# oresat-backplane-1u.net
KiCad netlist of a schematic drawn in EAGLE
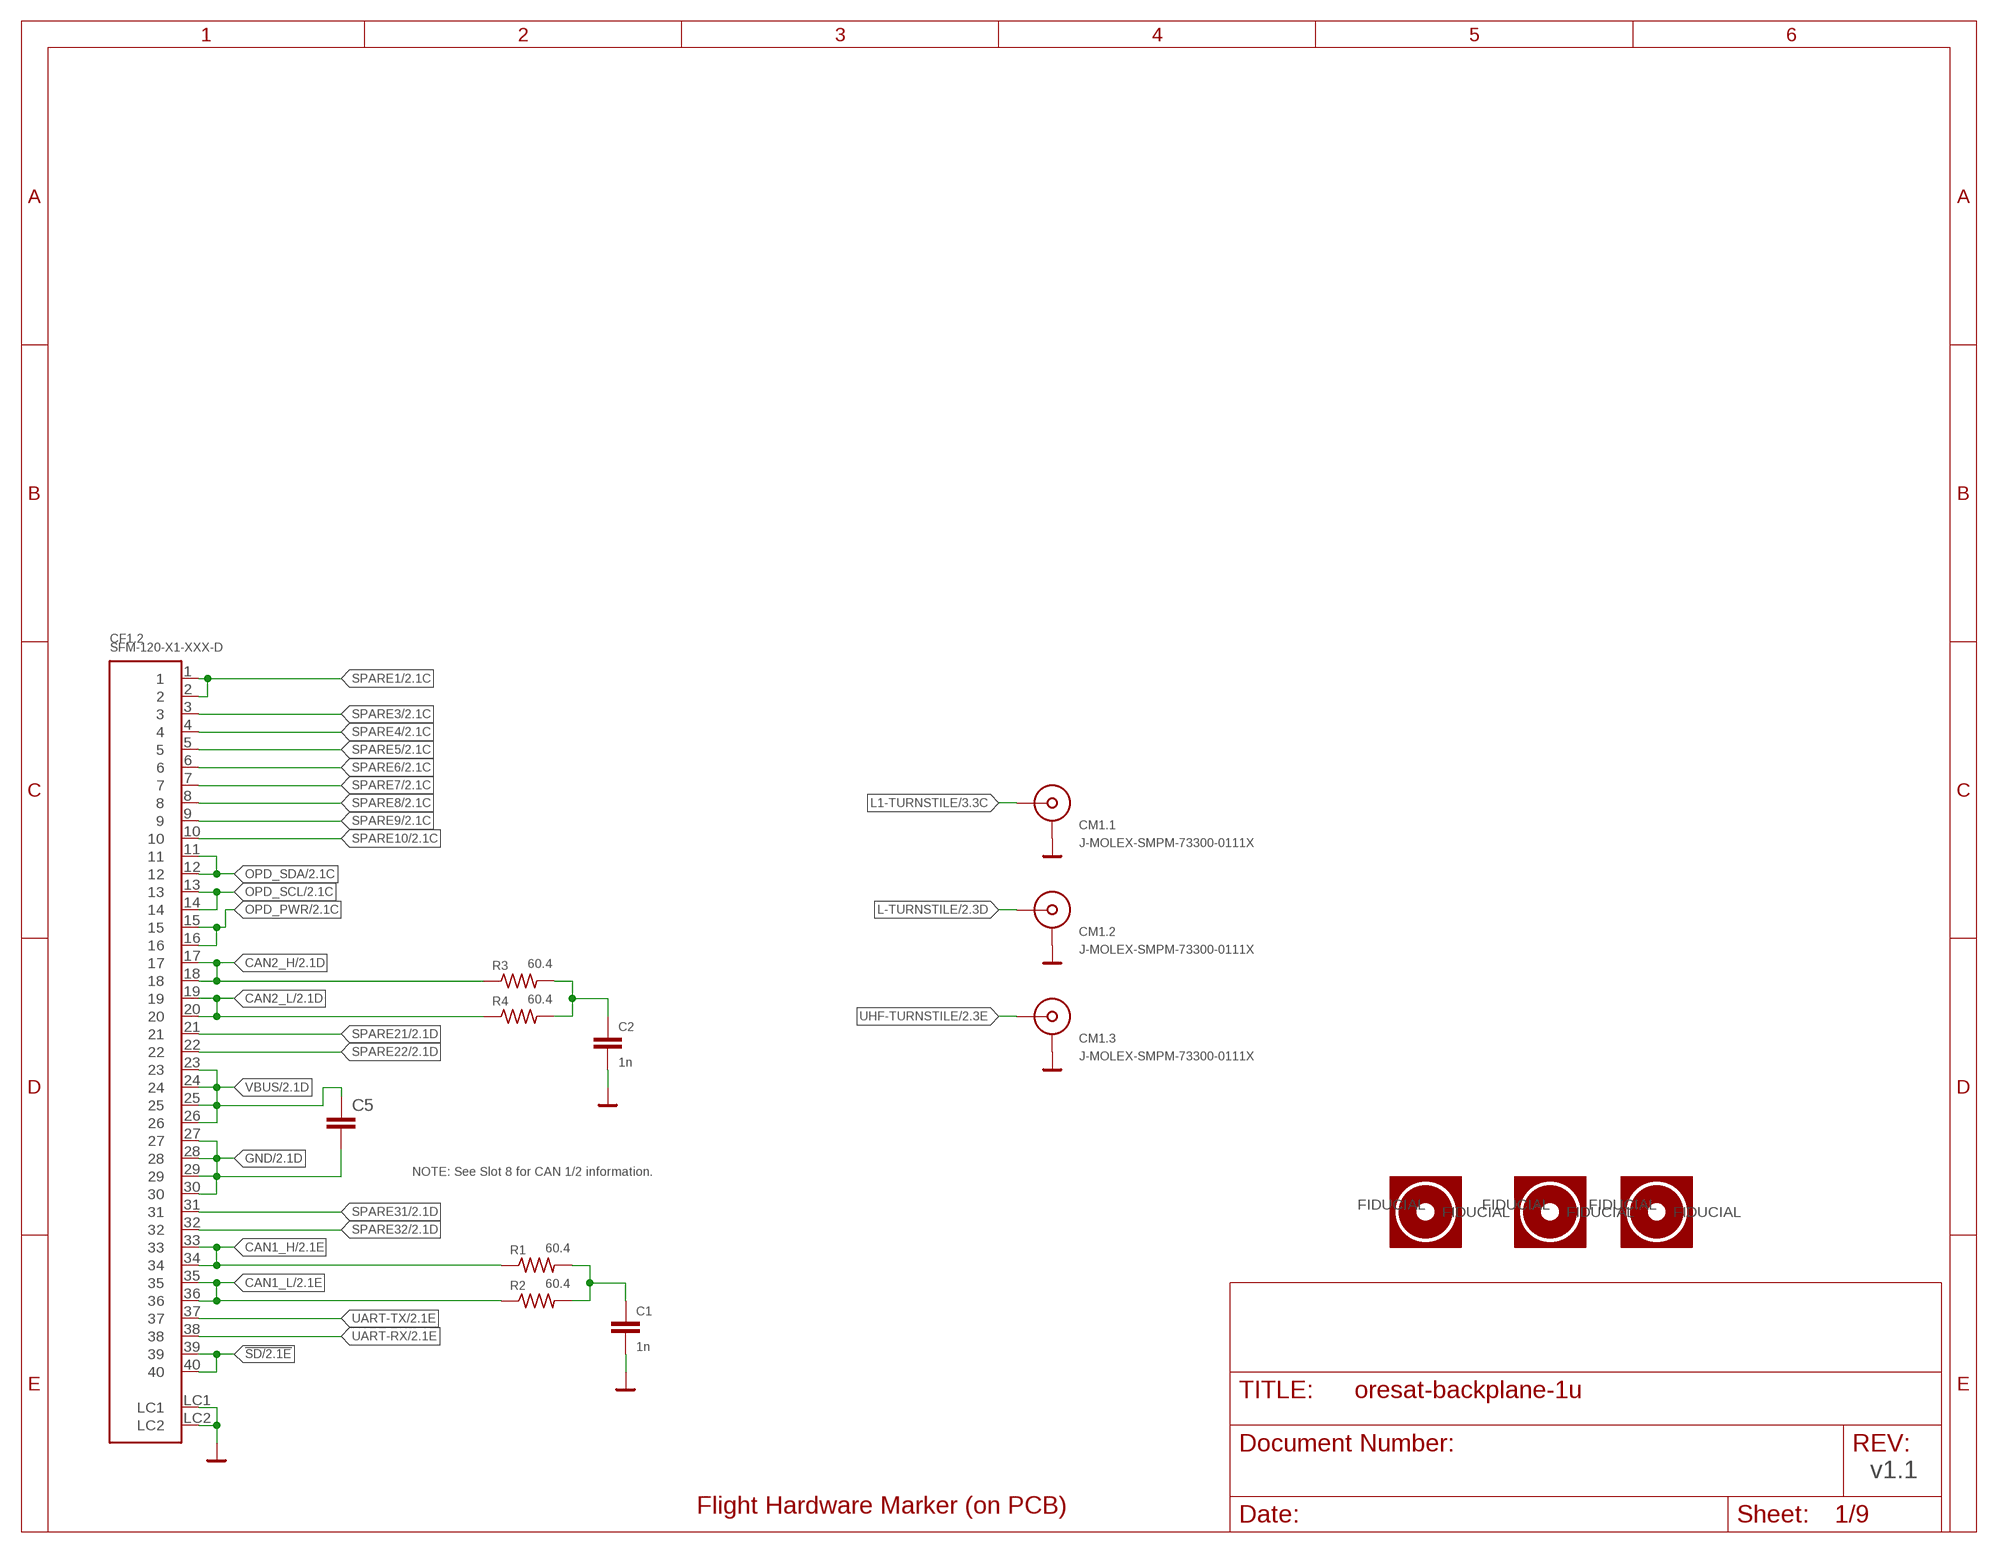
[diagram p0: schematic, sheet 1]
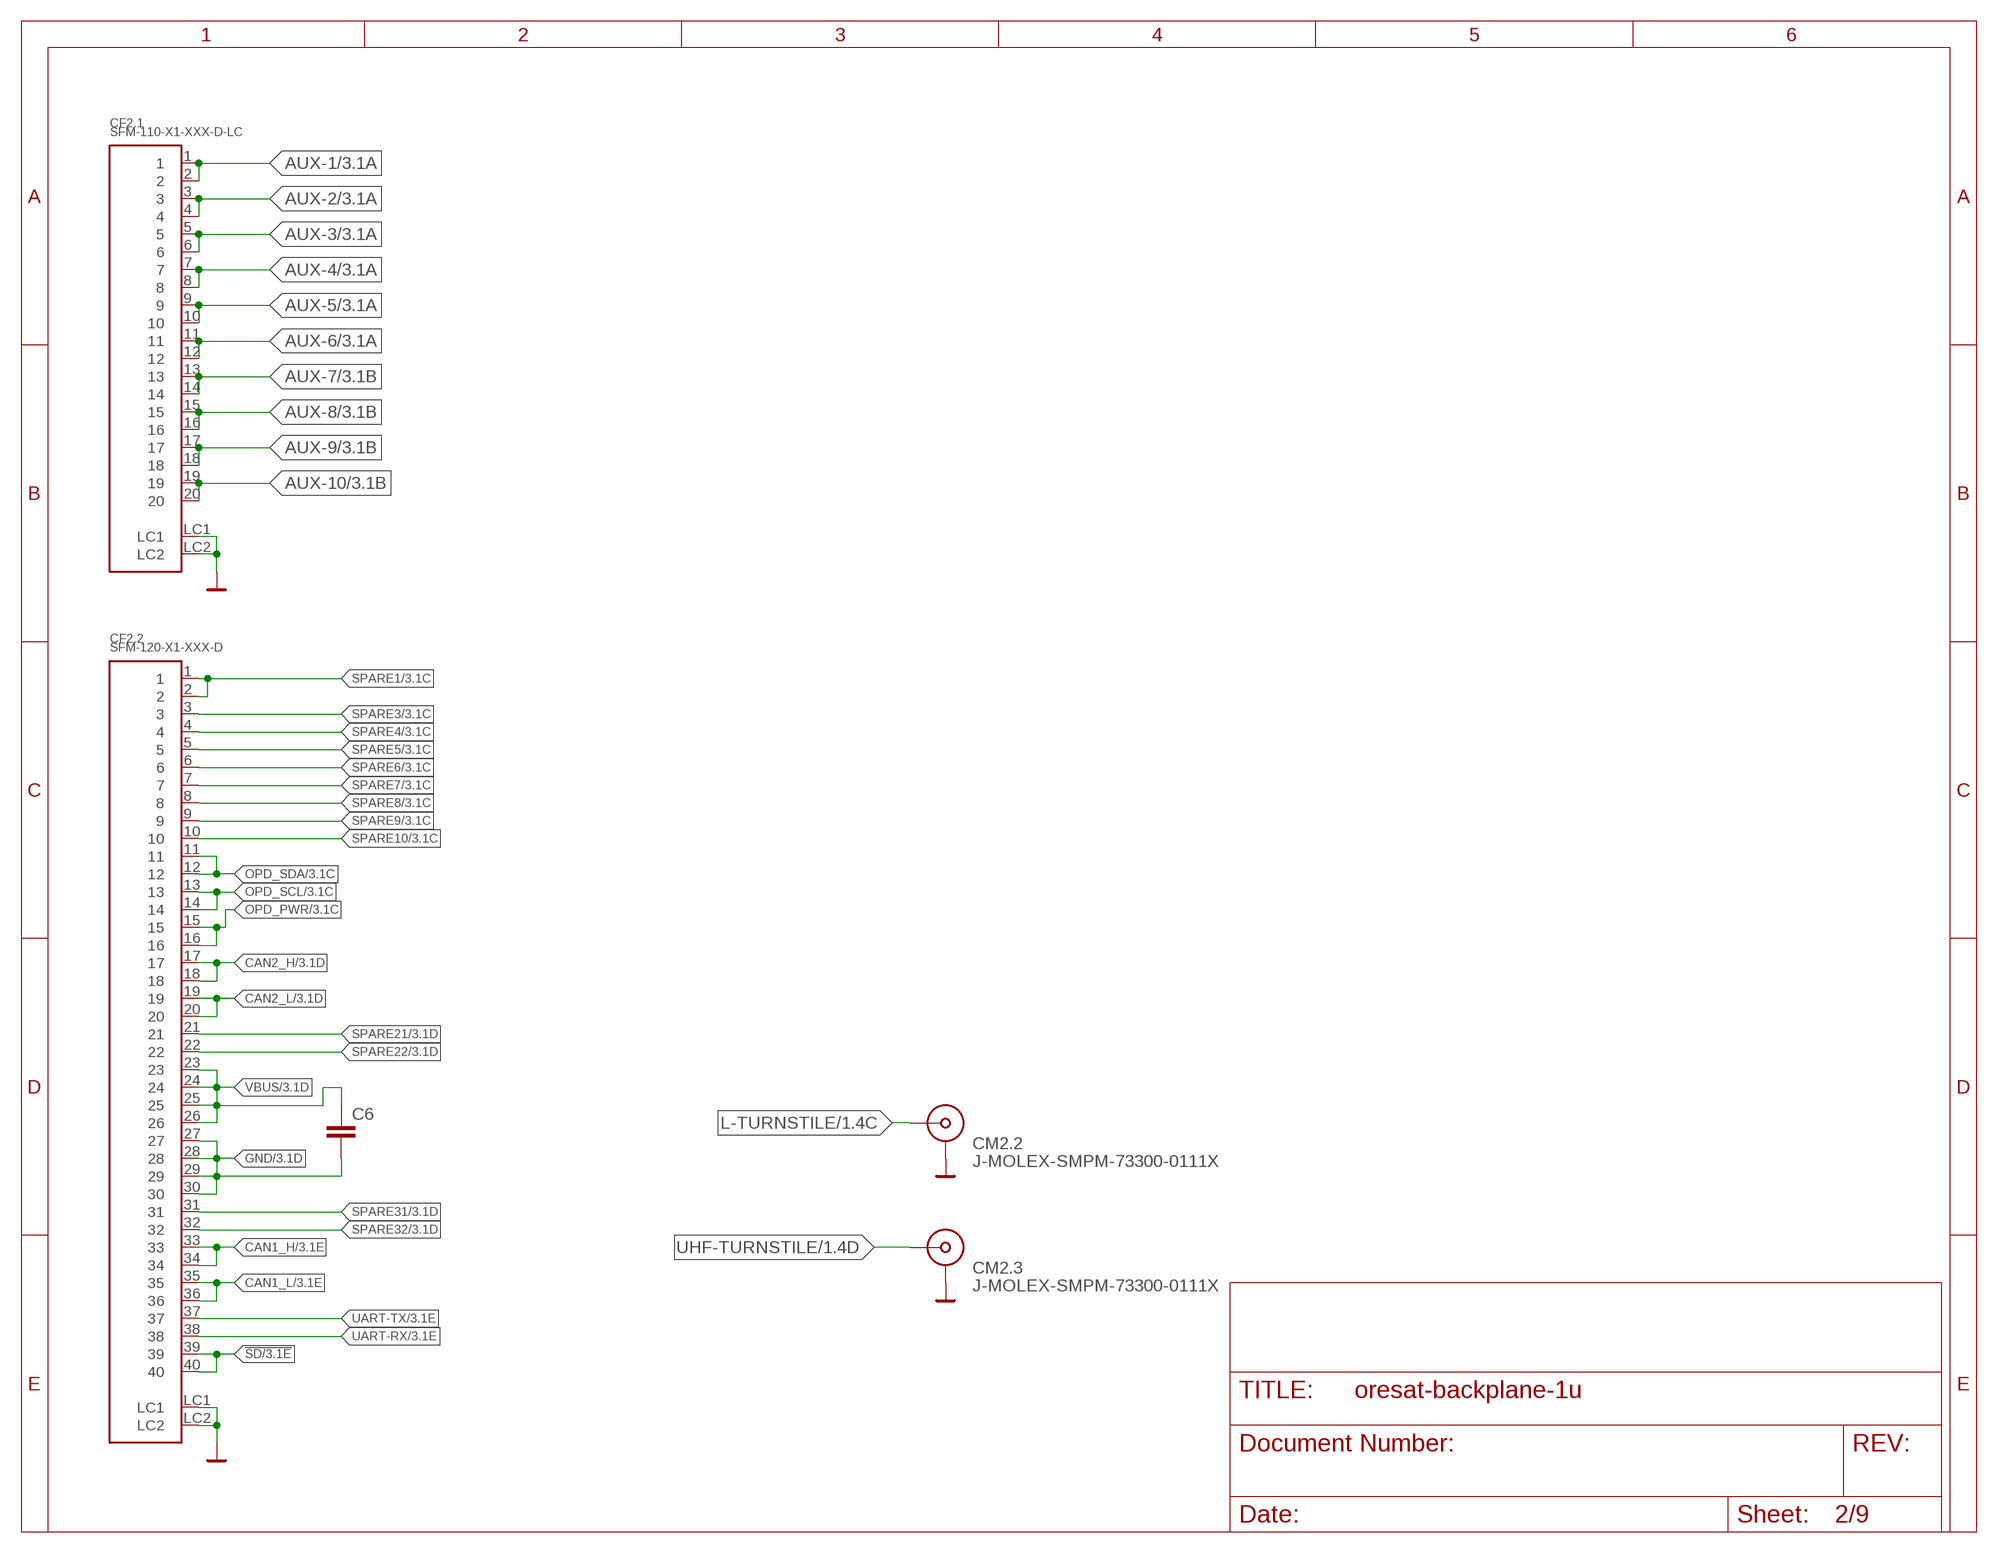
[diagram p1: schematic, sheet 2]
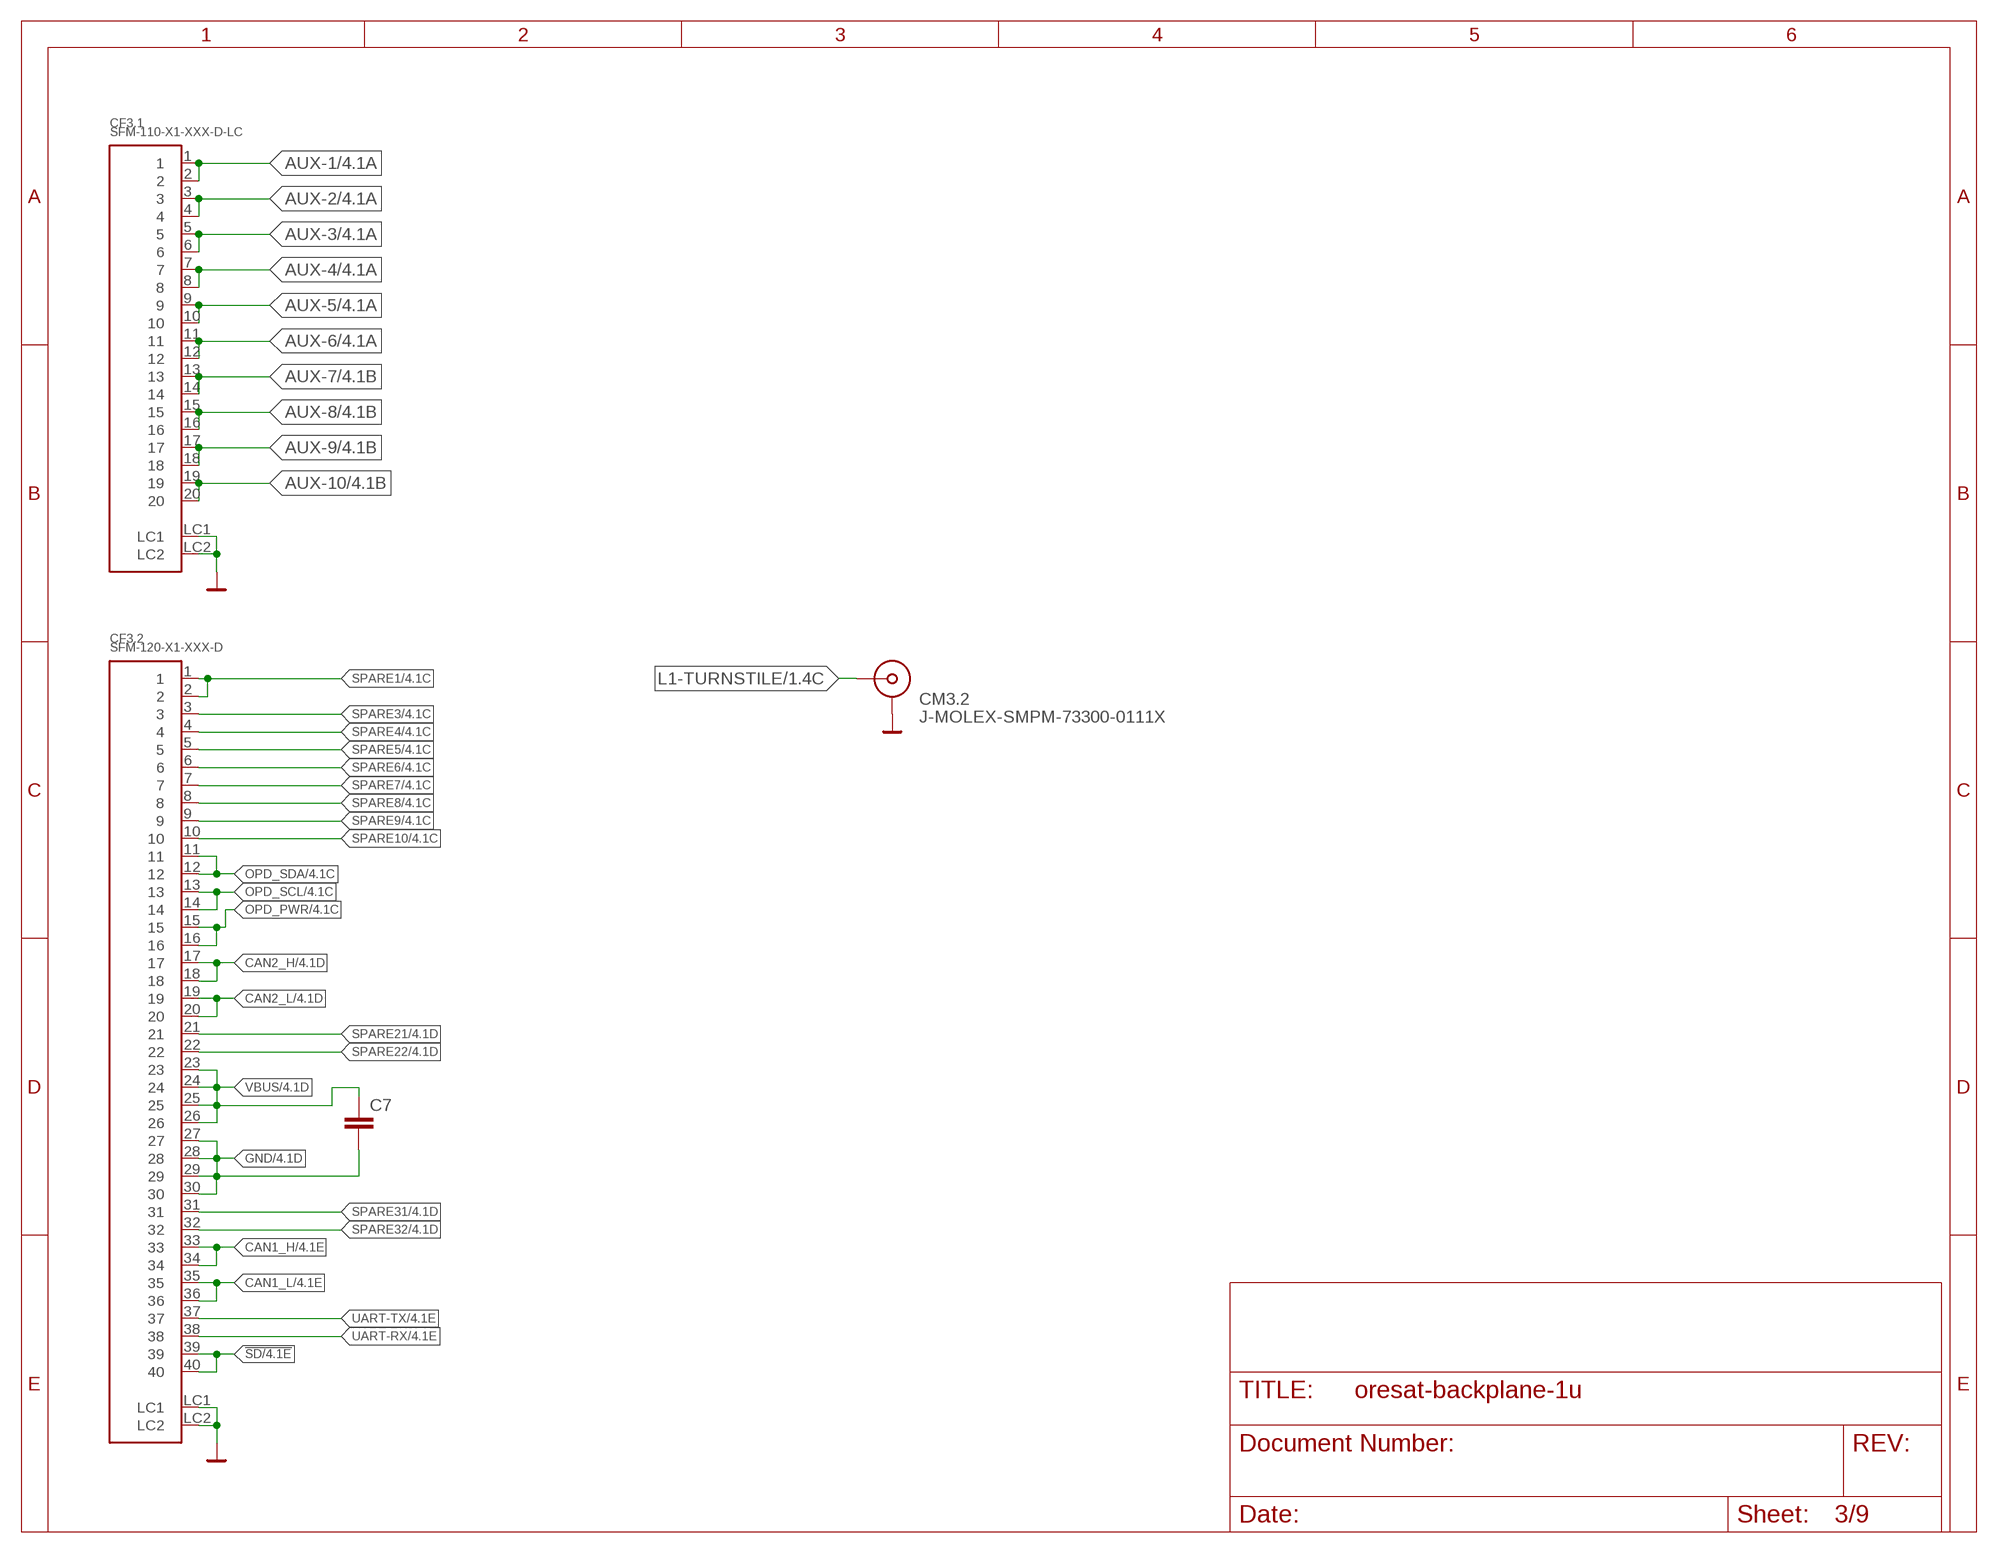
[diagram p2: schematic, sheet 3]
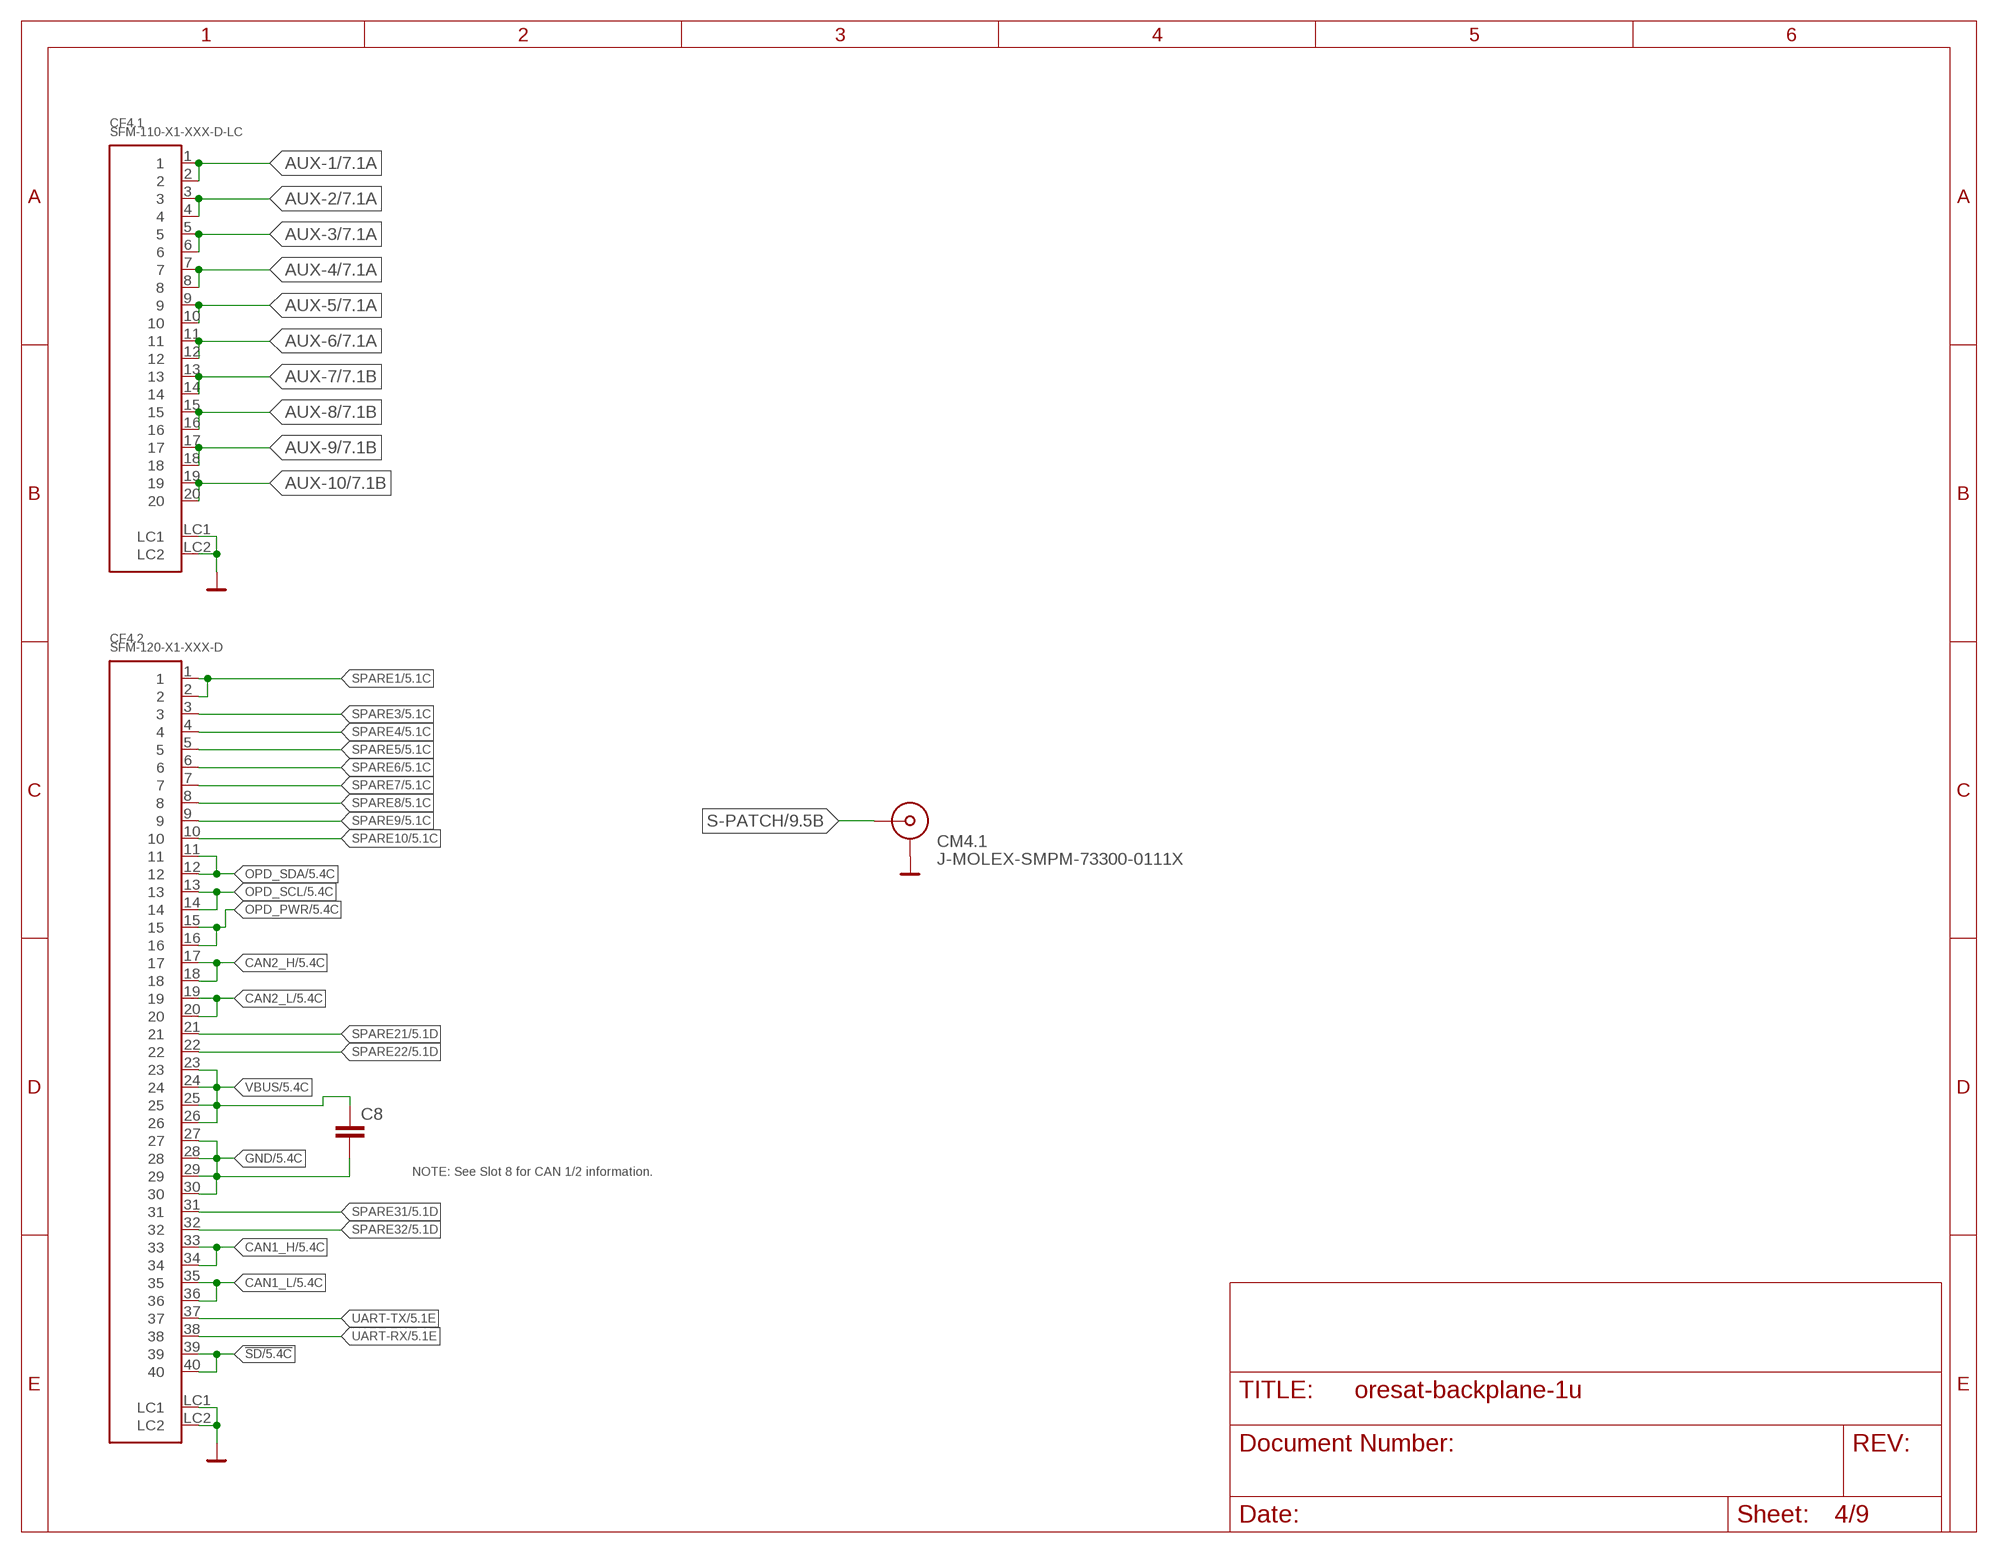
[diagram p3: schematic, sheet 4]
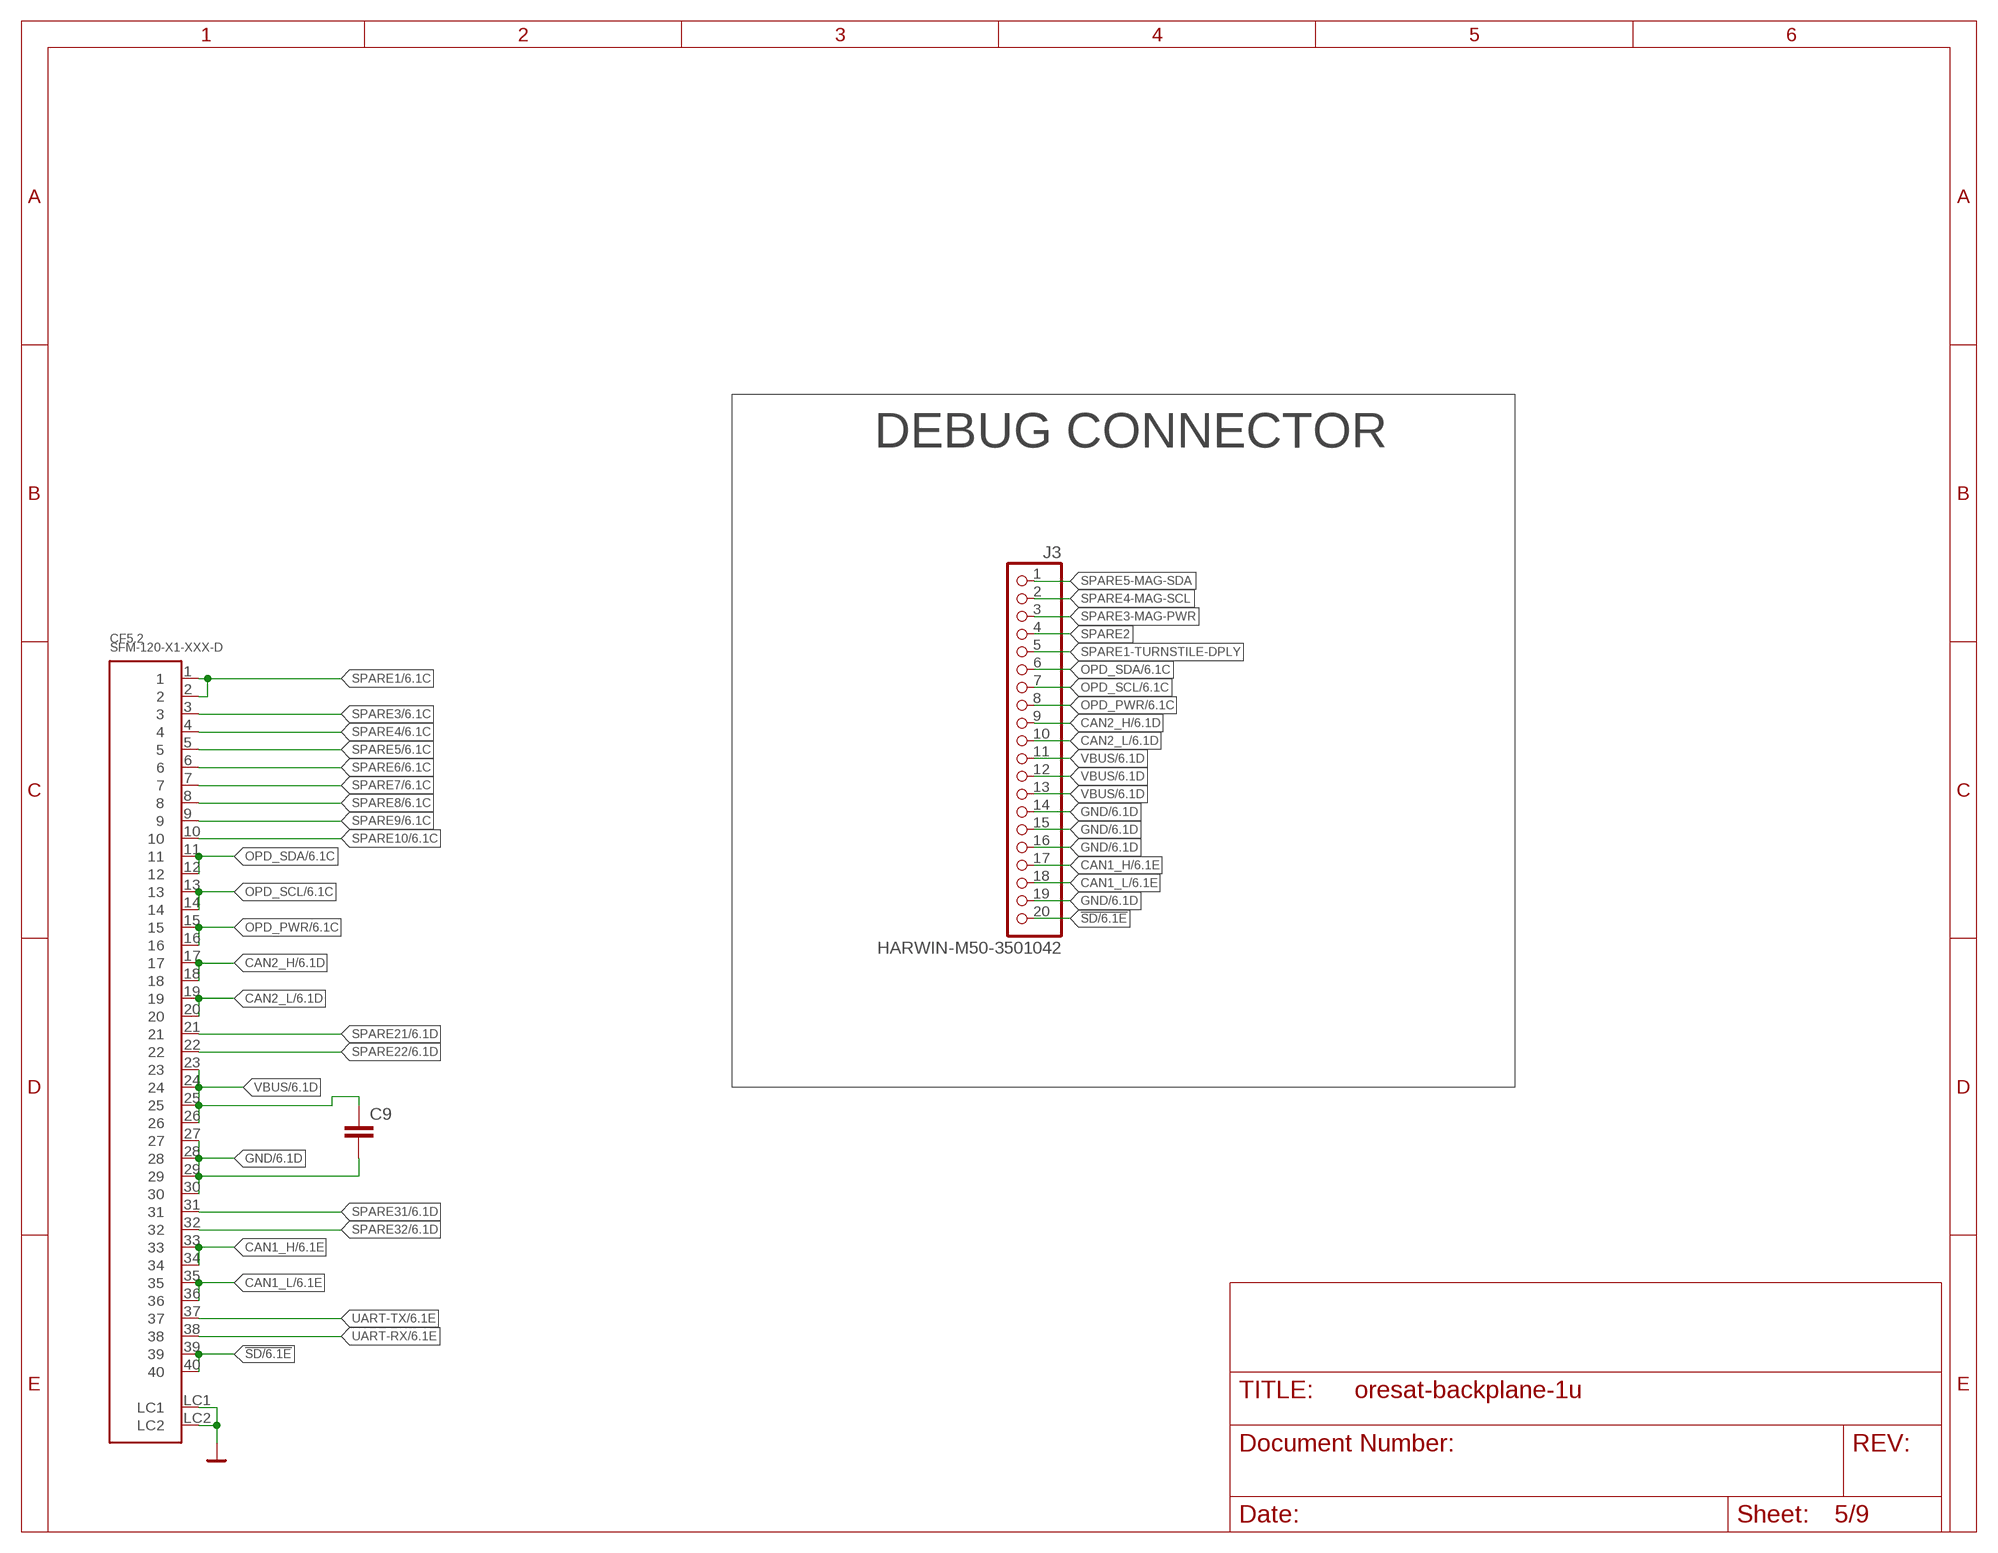
[diagram p4: schematic, sheet 5]
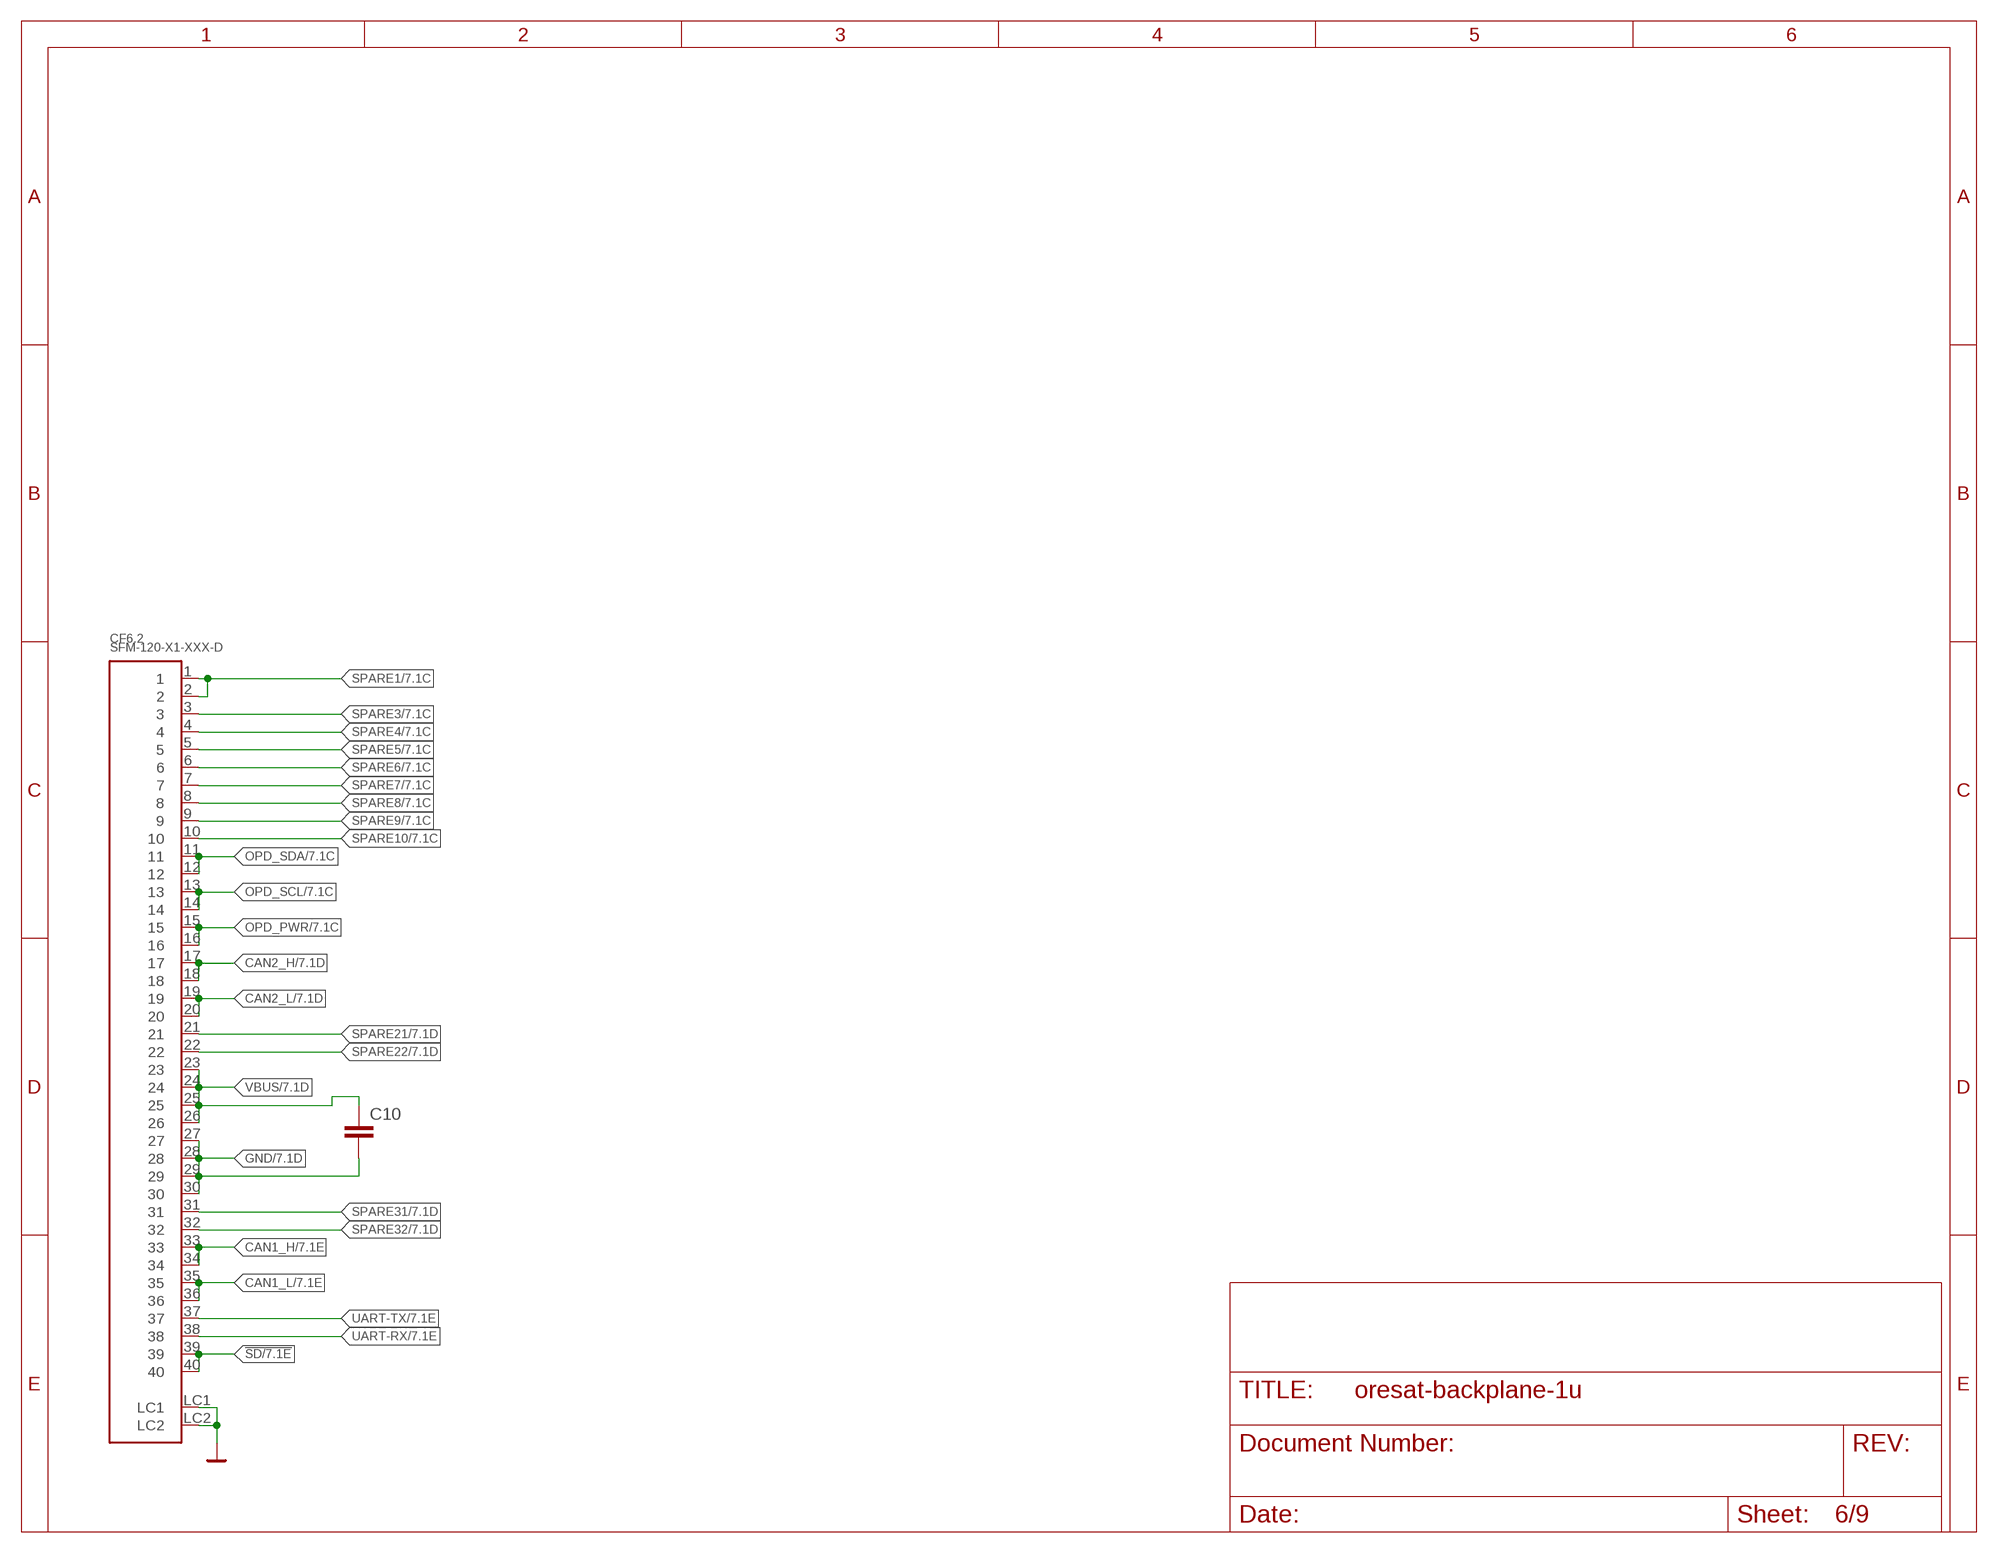
[diagram p5: schematic, sheet 6]
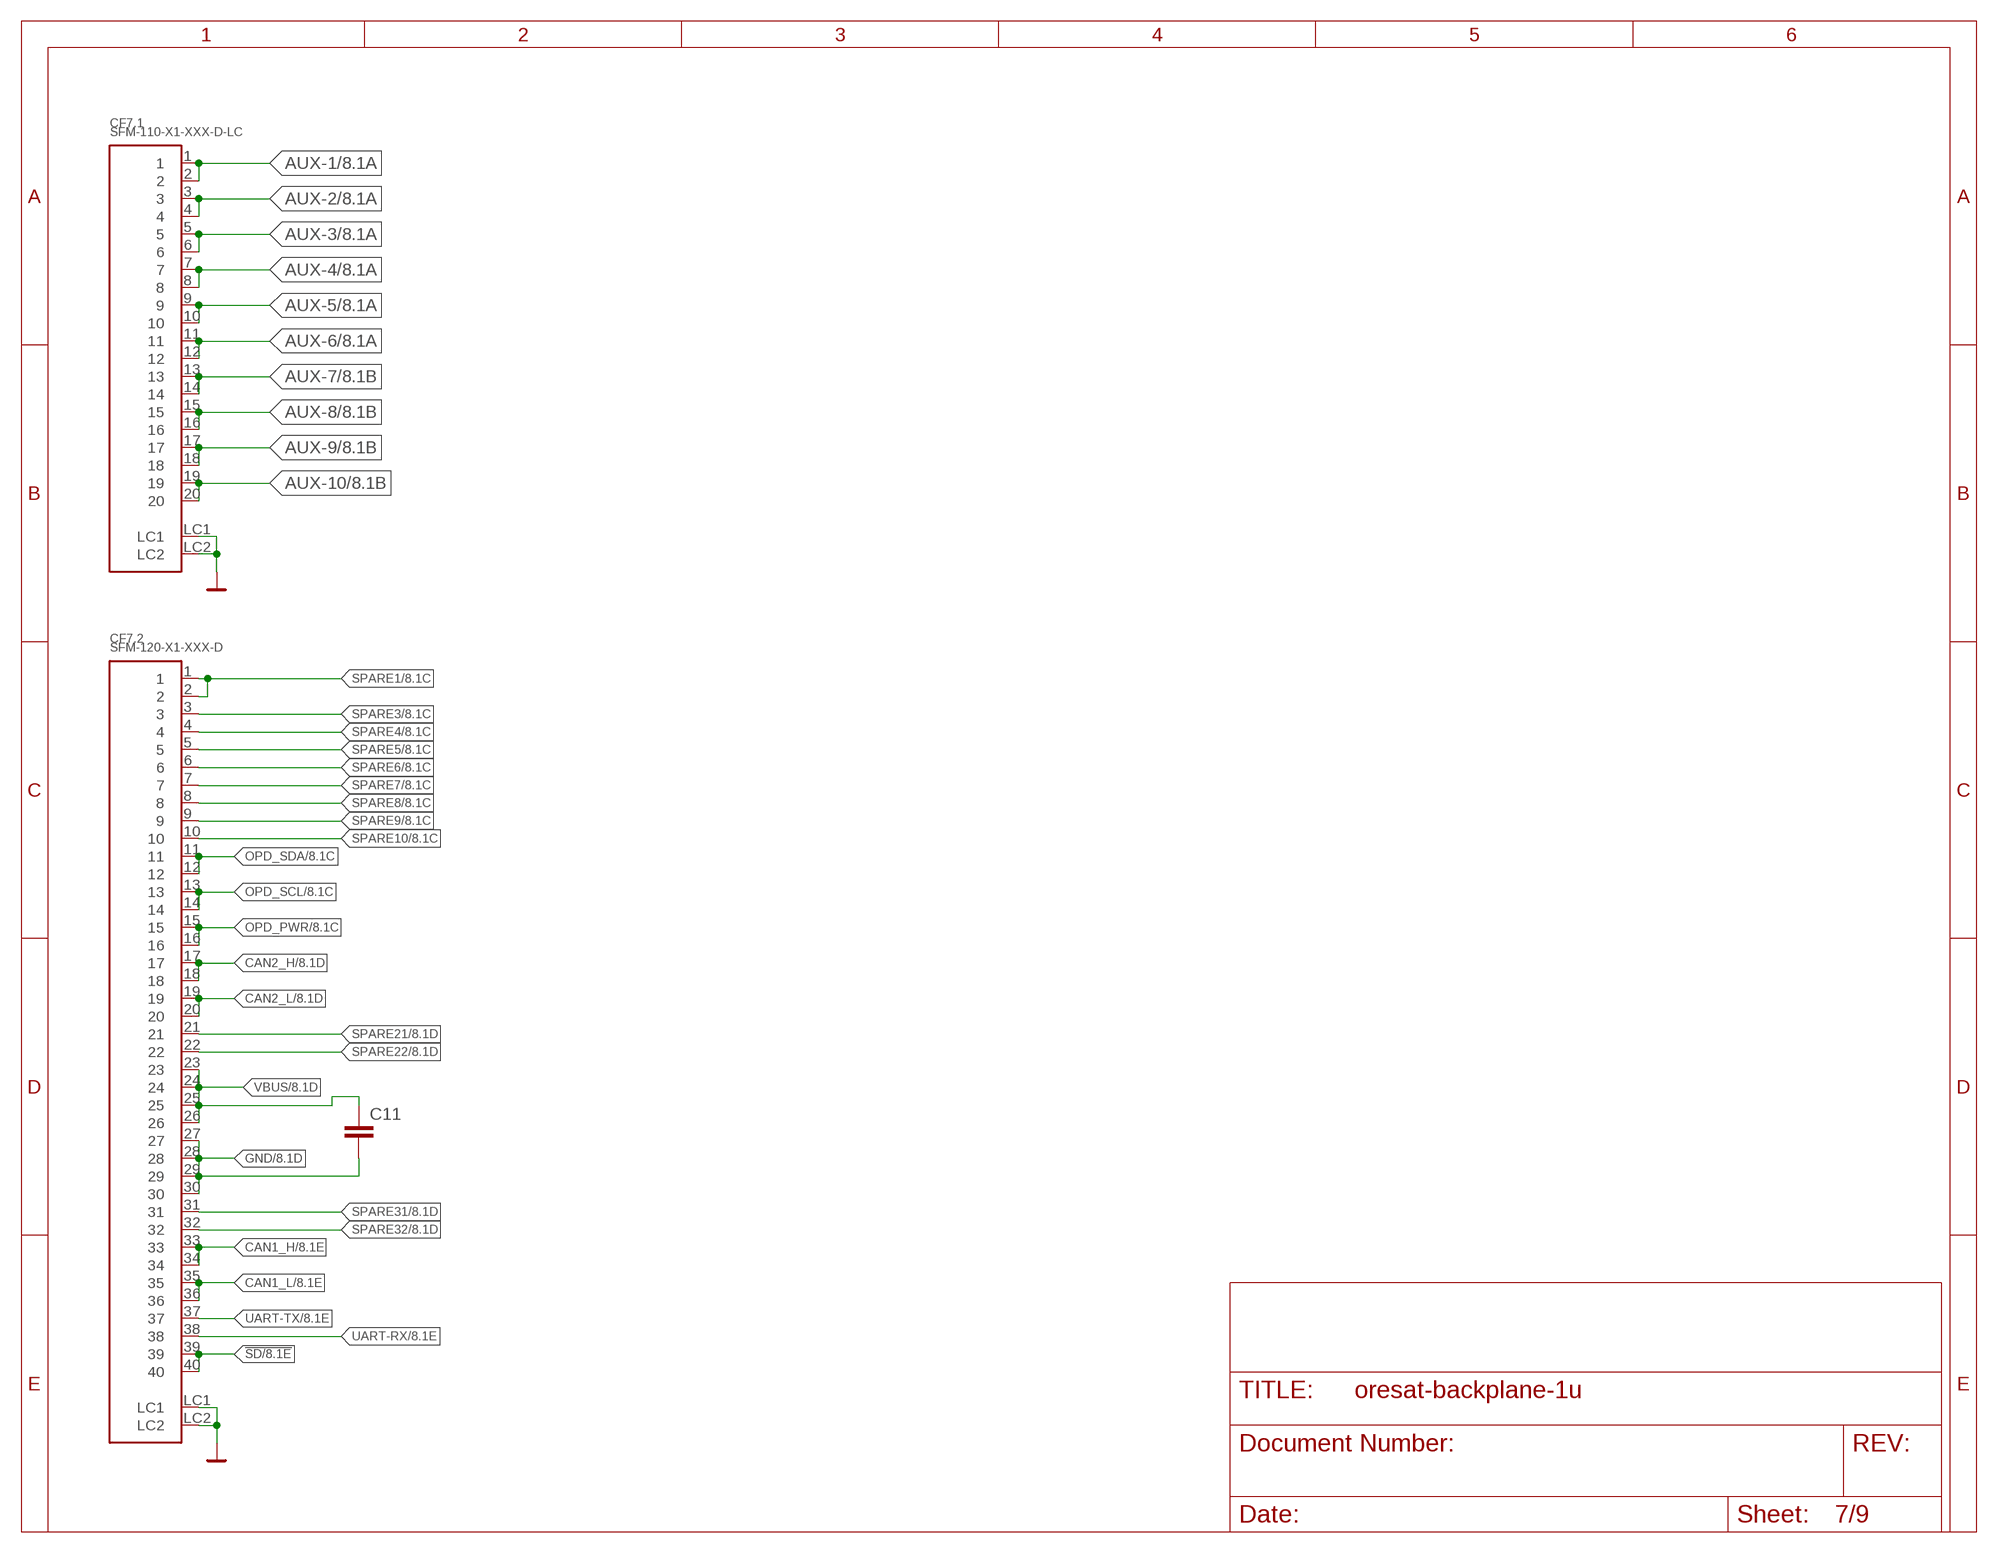
[diagram p6: schematic, sheet 7]
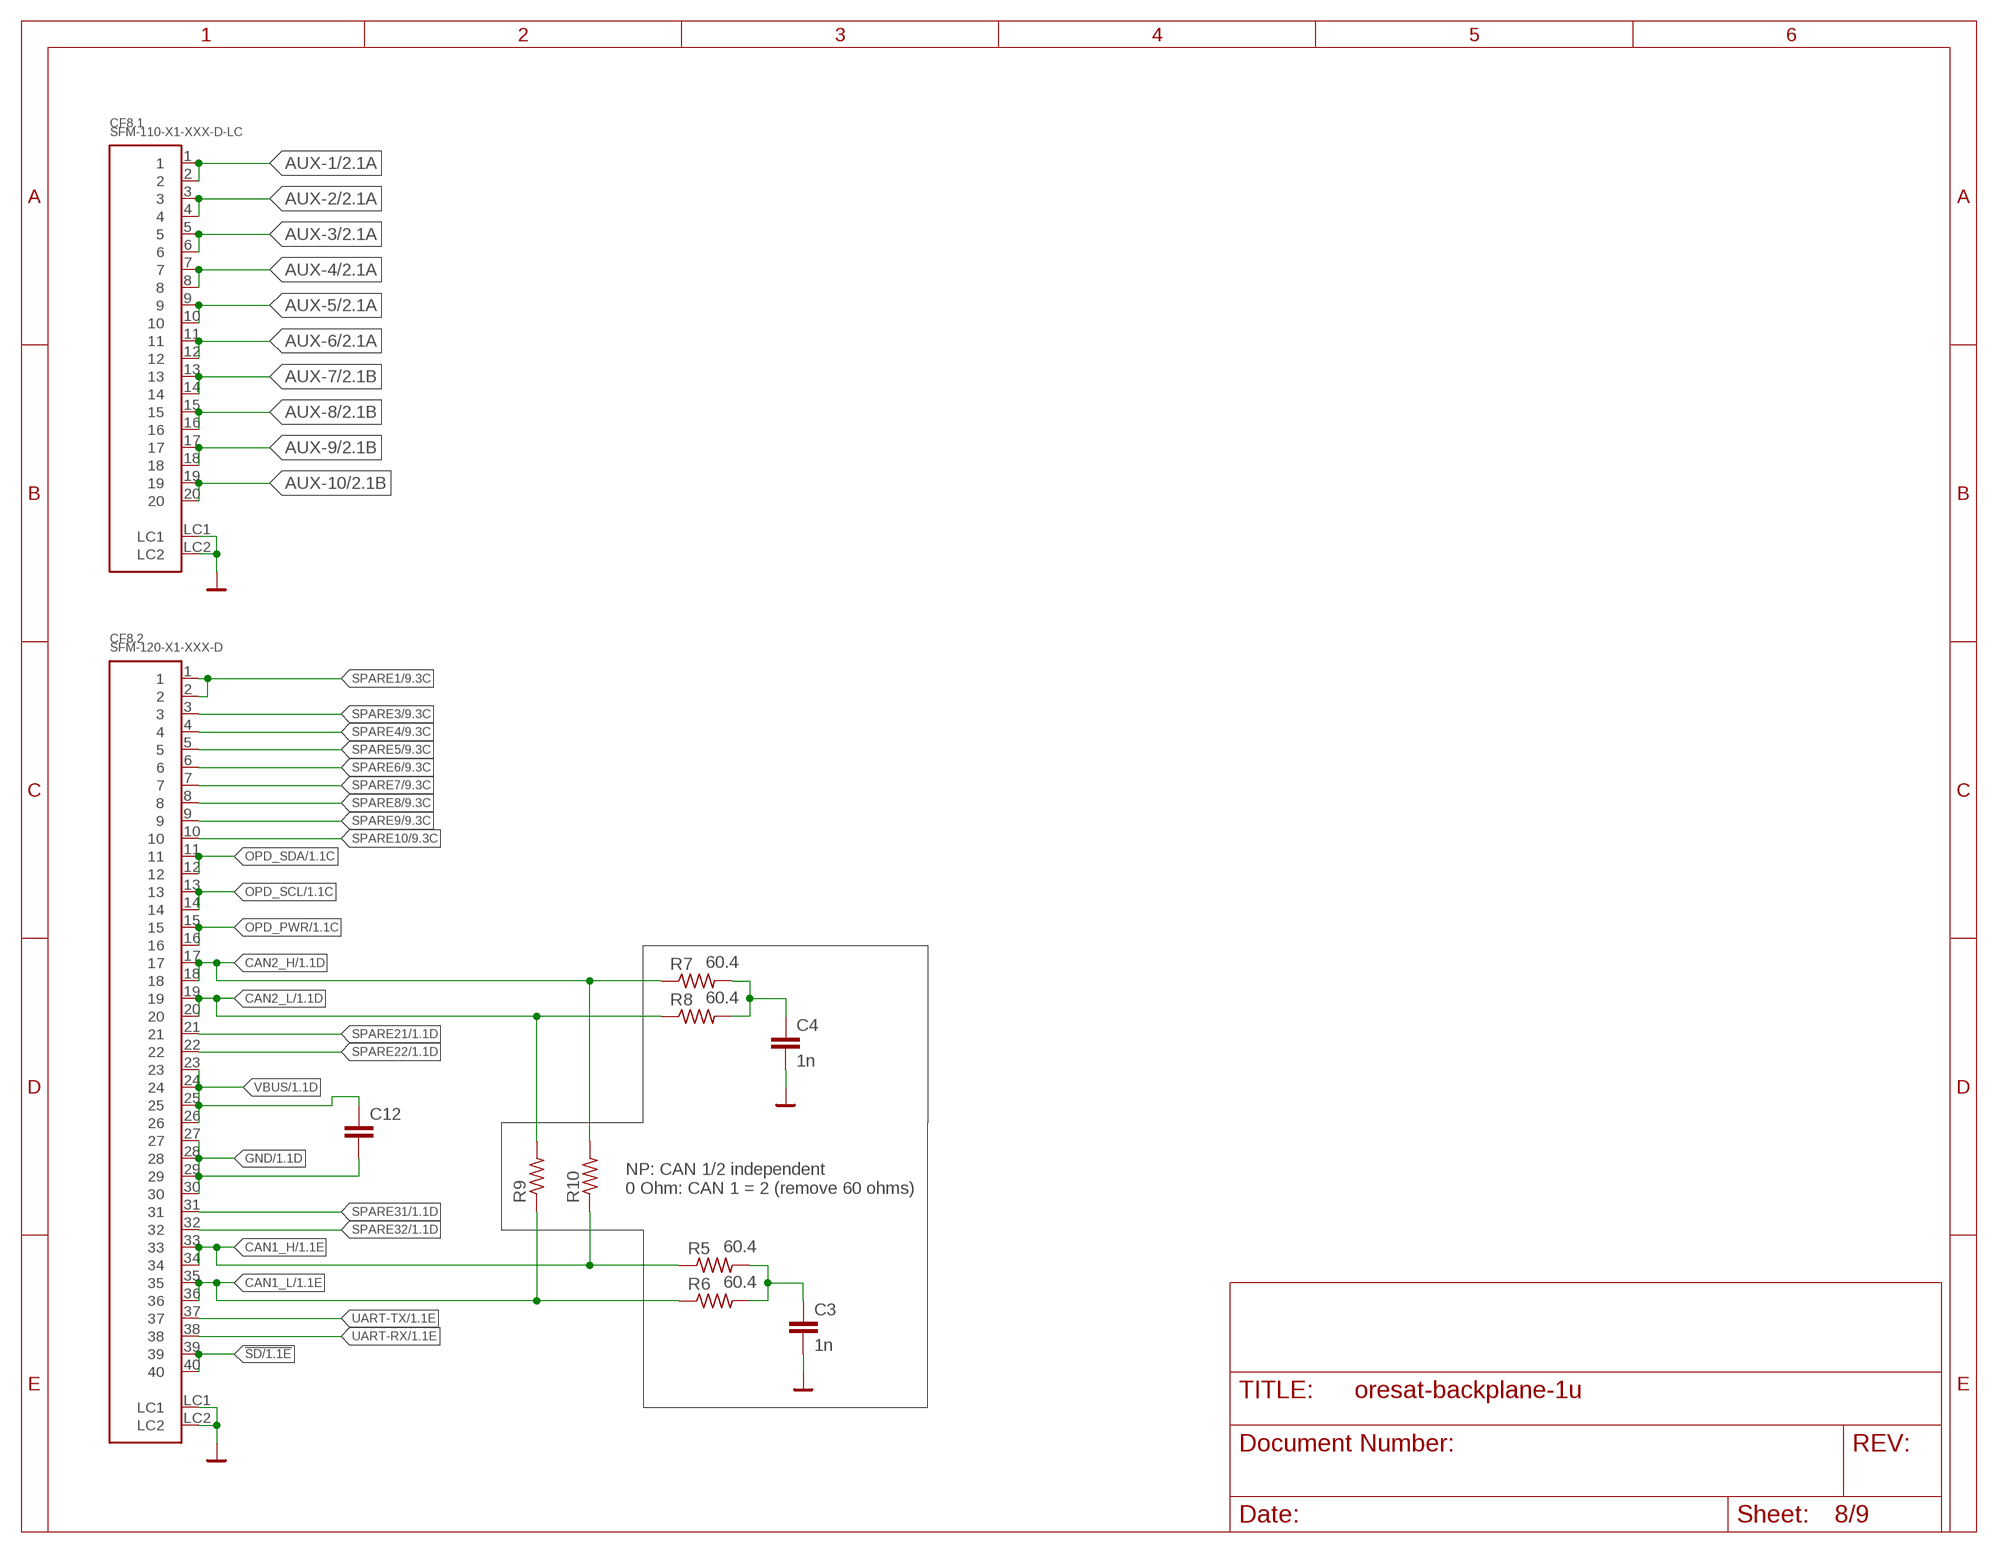
[diagram p7: schematic, sheet 8]
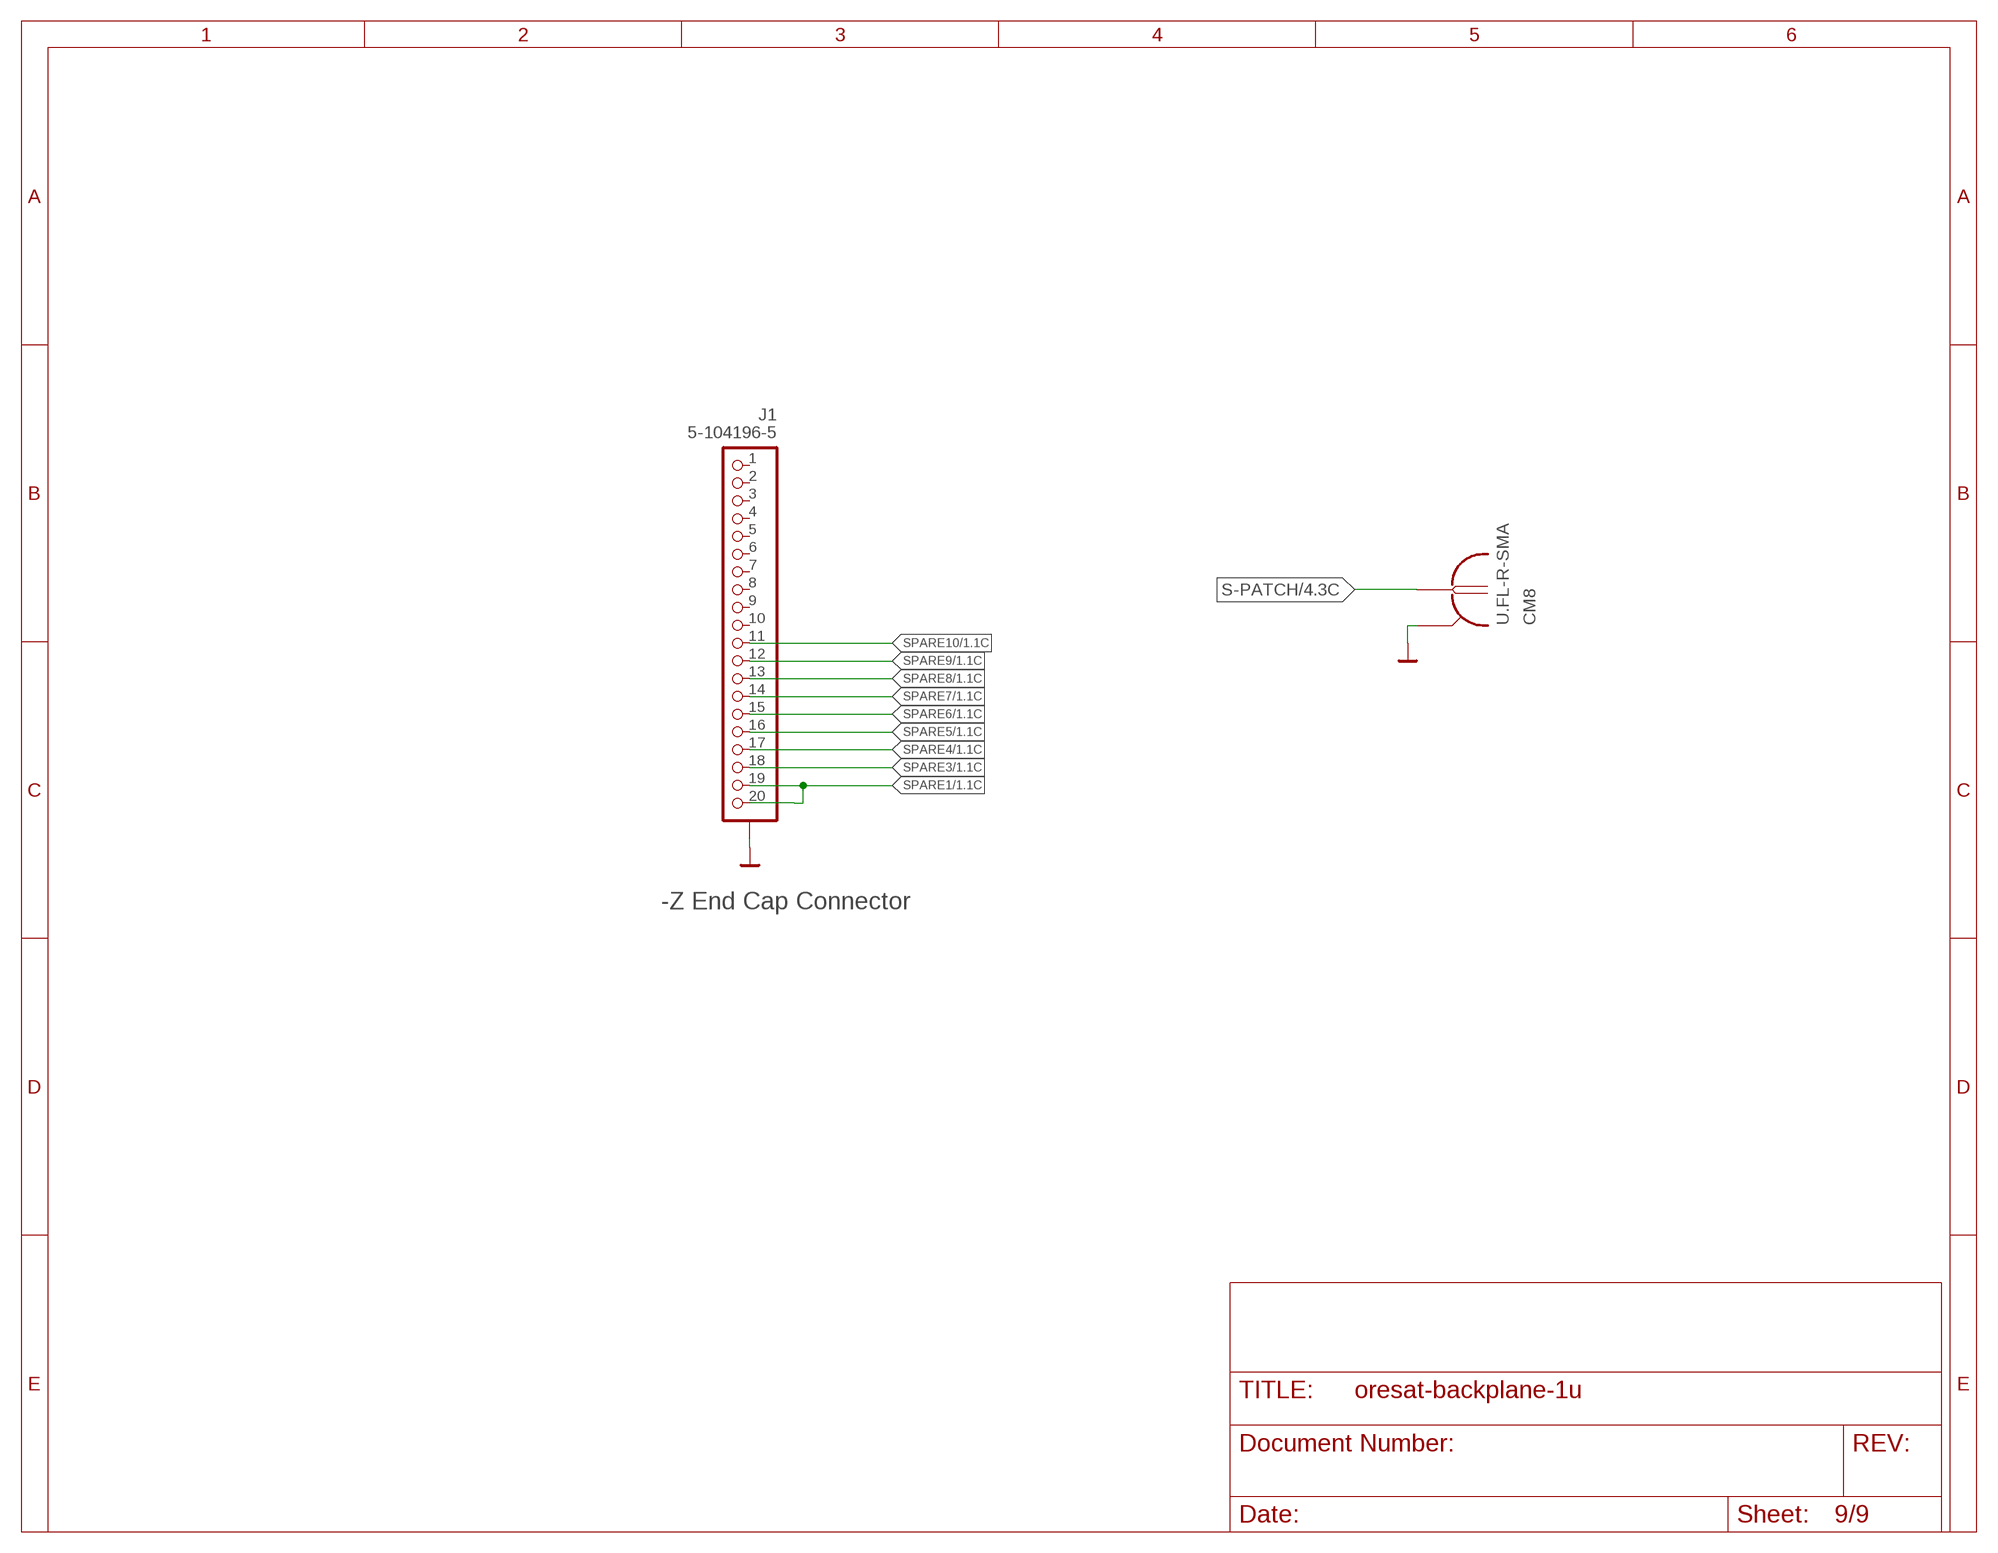
[diagram p8: schematic, sheet 9]

(export (version "E")
  (design (tool "Eeschema 10.0.6"))
  (components
    (comp (ref "C7")
      (value "C-EU1206-B")
      (footprint "eagle-import:1206-B")
      (libsource (lib "eagle-import") (part "C-EU1206-B"))
    )
    (comp (ref "CF3.1")
      (value "SFM-110-X1-XXX-D-LC")
      (footprint "eagle-import:SFM-110-X1-XXX-D-LC")
      (libsource (lib "eagle-import") (part "SFM-110-X1-XXX-D-LC"))
    )
    (comp (ref "CF3.2")
      (value "SFM-120-X1-XXX-D")
      (footprint "eagle-import:SFM-120-X1-XXX-D")
      (libsource (lib "eagle-import") (part "SFM-120-X1-XXX-D"))
    )
    (comp (ref "CM3.2")
      (value "J-MOLEX-SMPM-73300-0111X")
      (footprint "eagle-import:J-MOLEX-SMPM-73300-0111X")
      (libsource (lib "eagle-import") (part "J-MOLEX-SMPM-73300-0111X"))
    )
    (comp (ref "C9")
      (value "C-EU1206-B")
      (footprint "eagle-import:1206-B")
      (libsource (lib "eagle-import") (part "C-EU1206-B"))
    )
    (comp (ref "CF5.2")
      (value "SFM-120-X1-XXX-D")
      (footprint "eagle-import:SFM-120-X1-XXX-D")
      (libsource (lib "eagle-import") (part "SFM-120-X1-XXX-D"))
    )
    (comp (ref "J3")
      (value "HARWIN-M50-3501042")
      (footprint "eagle-import:HARWIN-M50-3501042")
      (libsource (lib "eagle-import") (part "HARWIN-M50-3501042"))
    )
    (comp (ref "C6")
      (value "C-EU1206-B")
      (footprint "eagle-import:1206-B")
      (libsource (lib "eagle-import") (part "C-EU1206-B"))
    )
    (comp (ref "CF2.1")
      (value "SFM-110-X1-XXX-D-LC")
      (footprint "eagle-import:SFM-110-X1-XXX-D-LC")
      (libsource (lib "eagle-import") (part "SFM-110-X1-XXX-D-LC"))
    )
    (comp (ref "CF2.2")
      (value "SFM-120-X1-XXX-D")
      (footprint "eagle-import:SFM-120-X1-XXX-D")
      (libsource (lib "eagle-import") (part "SFM-120-X1-XXX-D"))
    )
    (comp (ref "CM2.2")
      (value "J-MOLEX-SMPM-73300-0111X")
      (footprint "eagle-import:J-MOLEX-SMPM-73300-0111X")
      (libsource (lib "eagle-import") (part "J-MOLEX-SMPM-73300-0111X"))
    )
    (comp (ref "CM2.3")
      (value "J-MOLEX-SMPM-73300-0111X")
      (footprint "eagle-import:J-MOLEX-SMPM-73300-0111X")
      (libsource (lib "eagle-import") (part "J-MOLEX-SMPM-73300-0111X"))
    )
    (comp (ref "C1")
      (value "1n")
      (footprint "eagle-import:.0603-C-NOSILK")
      (libsource (lib "eagle-import") (part "C-EU0603-C-NOSILK"))
    )
    (comp (ref "C2")
      (value "1n")
      (footprint "eagle-import:.0603-C-NOSILK")
      (libsource (lib "eagle-import") (part "C-EU0603-C-NOSILK"))
    )
    (comp (ref "C5")
      (value "C-EU1206-B")
      (footprint "eagle-import:1206-B")
      (libsource (lib "eagle-import") (part "C-EU1206-B"))
    )
    (comp (ref "CF1.2")
      (value "SFM-120-X1-XXX-D")
      (footprint "eagle-import:SFM-120-X1-XXX-D")
      (libsource (lib "eagle-import") (part "SFM-120-X1-XXX-D"))
    )
    (comp (ref "CM1.1")
      (value "J-MOLEX-SMPM-73300-0111X")
      (footprint "eagle-import:J-MOLEX-SMPM-73300-0111X")
      (libsource (lib "eagle-import") (part "J-MOLEX-SMPM-73300-0111X"))
    )
    (comp (ref "CM1.2")
      (value "J-MOLEX-SMPM-73300-0111X")
      (footprint "eagle-import:J-MOLEX-SMPM-73300-0111X")
      (libsource (lib "eagle-import") (part "J-MOLEX-SMPM-73300-0111X"))
    )
    (comp (ref "CM1.3")
      (value "J-MOLEX-SMPM-73300-0111X")
      (footprint "eagle-import:J-MOLEX-SMPM-73300-0111X")
      (libsource (lib "eagle-import") (part "J-MOLEX-SMPM-73300-0111X"))
    )
    (comp (ref "FIDUCIAL1")
      (value "FIDUCIAL-1.0X2.0")
      (footprint "eagle-import:FIDUCIAL-1.0X2.0")
      (libsource (lib "eagle-import") (part "FIDUCIAL-1.0X2.0"))
    )
    (comp (ref "FIDUCIAL2")
      (value "FIDUCIAL-1.0X2.0")
      (footprint "eagle-import:FIDUCIAL-1.0X2.0")
      (libsource (lib "eagle-import") (part "FIDUCIAL-1.0X2.0"))
    )
    (comp (ref "FIDUCIAL3")
      (value "FIDUCIAL-1.0X2.0")
      (footprint "eagle-import:FIDUCIAL-1.0X2.0")
      (libsource (lib "eagle-import") (part "FIDUCIAL-1.0X2.0"))
    )
    (comp (ref "R1")
      (value "60.4")
      (footprint "eagle-import:1206-C")
      (libsource (lib "eagle-import") (part "R-US_1206-C"))
    )
    (comp (ref "R2")
      (value "60.4")
      (footprint "eagle-import:1206-C")
      (libsource (lib "eagle-import") (part "R-US_1206-C"))
    )
    (comp (ref "R3")
      (value "60.4")
      (footprint "eagle-import:1206-C")
      (libsource (lib "eagle-import") (part "R-US_1206-C"))
    )
    (comp (ref "R4")
      (value "60.4")
      (footprint "eagle-import:1206-C")
      (libsource (lib "eagle-import") (part "R-US_1206-C"))
    )
    (comp (ref "U$1")
      (value "FLIGHMARKERNEW")
      (footprint "eagle-import:FLIGHTMARKER_NEW_BOARDS")
      (libsource (lib "eagle-import") (part "FLIGHMARKERNEW"))
    )
    (comp (ref "C3")
      (value "1n")
      (footprint "eagle-import:.0603-C-NOSILK")
      (libsource (lib "eagle-import") (part "C-EU0603-C-NOSILK"))
    )
    (comp (ref "C4")
      (value "1n")
      (footprint "eagle-import:.0603-C-NOSILK")
      (libsource (lib "eagle-import") (part "C-EU0603-C-NOSILK"))
    )
    (comp (ref "C12")
      (value "C-EU1206-B")
      (footprint "eagle-import:1206-B")
      (libsource (lib "eagle-import") (part "C-EU1206-B"))
    )
    (comp (ref "CF8.1")
      (value "SFM-110-X1-XXX-D-LC")
      (footprint "eagle-import:SFM-110-X1-XXX-D-LC")
      (libsource (lib "eagle-import") (part "SFM-110-X1-XXX-D-LC"))
    )
    (comp (ref "CF8.2")
      (value "SFM-120-X1-XXX-D")
      (footprint "eagle-import:SFM-120-X1-XXX-D")
      (libsource (lib "eagle-import") (part "SFM-120-X1-XXX-D"))
    )
    (comp (ref "R5")
      (value "60.4")
      (footprint "eagle-import:1206-C")
      (libsource (lib "eagle-import") (part "R-US_1206-C"))
    )
    (comp (ref "R6")
      (value "60.4")
      (footprint "eagle-import:1206-C")
      (libsource (lib "eagle-import") (part "R-US_1206-C"))
    )
    (comp (ref "R7")
      (value "60.4")
      (footprint "eagle-import:1206-C")
      (libsource (lib "eagle-import") (part "R-US_1206-C"))
    )
    (comp (ref "R8")
      (value "60.4")
      (footprint "eagle-import:1206-C")
      (libsource (lib "eagle-import") (part "R-US_1206-C"))
    )
    (comp (ref "R9")
      (value "R-US_0603-B-NOSILK")
      (footprint "eagle-import:.0603-B-NOSILK")
      (libsource (lib "eagle-import") (part "R-US_0603-B-NOSILK"))
    )
    (comp (ref "R10")
      (value "R-US_0603-B-NOSILK")
      (footprint "eagle-import:.0603-B-NOSILK")
      (libsource (lib "eagle-import") (part "R-US_0603-B-NOSILK"))
    )
    (comp (ref "C8")
      (value "C-EU1206-B")
      (footprint "eagle-import:1206-B")
      (libsource (lib "eagle-import") (part "C-EU1206-B"))
    )
    (comp (ref "CF4.1")
      (value "SFM-110-X1-XXX-D-LC")
      (footprint "eagle-import:SFM-110-X1-XXX-D-LC")
      (libsource (lib "eagle-import") (part "SFM-110-X1-XXX-D-LC"))
    )
    (comp (ref "CF4.2")
      (value "SFM-120-X1-XXX-D")
      (footprint "eagle-import:SFM-120-X1-XXX-D")
      (libsource (lib "eagle-import") (part "SFM-120-X1-XXX-D"))
    )
    (comp (ref "CM4.1")
      (value "J-MOLEX-SMPM-73300-0111X")
      (footprint "eagle-import:J-MOLEX-SMPM-73300-0111X")
      (libsource (lib "eagle-import") (part "J-MOLEX-SMPM-73300-0111X"))
    )
    (comp (ref "C10")
      (value "C-EU1206-B")
      (footprint "eagle-import:1206-B")
      (libsource (lib "eagle-import") (part "C-EU1206-B"))
    )
    (comp (ref "CF6.2")
      (value "SFM-120-X1-XXX-D")
      (footprint "eagle-import:SFM-120-X1-XXX-D")
      (libsource (lib "eagle-import") (part "SFM-120-X1-XXX-D"))
    )
    (comp (ref "CM8")
      (value "U.FL-R-SMA")
      (footprint "eagle-import:U.FL-R-SMT")
      (libsource (lib "eagle-import") (part "U.FL-R-SMA"))
    )
    (comp (ref "J1")
      (value "5-104196-5")
      (footprint "eagle-import:5-104196-5")
      (libsource (lib "eagle-import") (part "5-104196-5"))
    )
    (comp (ref "C11")
      (value "C-EU1206-B")
      (footprint "eagle-import:1206-B")
      (libsource (lib "eagle-import") (part "C-EU1206-B"))
    )
    (comp (ref "CF7.1")
      (value "SFM-110-X1-XXX-D-LC")
      (footprint "eagle-import:SFM-110-X1-XXX-D-LC")
      (libsource (lib "eagle-import") (part "SFM-110-X1-XXX-D-LC"))
    )
    (comp (ref "CF7.2")
      (value "SFM-120-X1-XXX-D")
      (footprint "eagle-import:SFM-120-X1-XXX-D")
      (libsource (lib "eagle-import") (part "SFM-120-X1-XXX-D"))
    )
  )
  (nets
    (net (code "1") (name "AUX-1") (class "Default")
      (node (ref "CF2.1") (pin "1") (pinfunction "1_1") (pintype "passive"))
      (node (ref "CF2.1") (pin "2") (pinfunction "2_2") (pintype "passive"))
      (node (ref "CF3.1") (pin "1") (pinfunction "1_1") (pintype "passive"))
      (node (ref "CF3.1") (pin "2") (pinfunction "2_2") (pintype "passive"))
      (node (ref "CF4.1") (pin "1") (pinfunction "1_1") (pintype "passive"))
      (node (ref "CF4.1") (pin "2") (pinfunction "2_2") (pintype "passive"))
      (node (ref "CF7.1") (pin "1") (pinfunction "1_1") (pintype "passive"))
      (node (ref "CF7.1") (pin "2") (pinfunction "2_2") (pintype "passive"))
      (node (ref "CF8.1") (pin "1") (pinfunction "1_1") (pintype "passive"))
      (node (ref "CF8.1") (pin "2") (pinfunction "2_2") (pintype "passive"))
    )
    (net (code "2") (name "AUX-2") (class "Default")
      (node (ref "CF2.1") (pin "3") (pinfunction "3_3") (pintype "passive"))
      (node (ref "CF2.1") (pin "4") (pinfunction "4_4") (pintype "passive"))
      (node (ref "CF3.1") (pin "3") (pinfunction "3_3") (pintype "passive"))
      (node (ref "CF3.1") (pin "4") (pinfunction "4_4") (pintype "passive"))
      (node (ref "CF4.1") (pin "3") (pinfunction "3_3") (pintype "passive"))
      (node (ref "CF4.1") (pin "4") (pinfunction "4_4") (pintype "passive"))
      (node (ref "CF7.1") (pin "3") (pinfunction "3_3") (pintype "passive"))
      (node (ref "CF7.1") (pin "4") (pinfunction "4_4") (pintype "passive"))
      (node (ref "CF8.1") (pin "3") (pinfunction "3_3") (pintype "passive"))
      (node (ref "CF8.1") (pin "4") (pinfunction "4_4") (pintype "passive"))
    )
    (net (code "3") (name "AUX-3") (class "Default")
      (node (ref "CF2.1") (pin "5") (pinfunction "5_5") (pintype "passive"))
      (node (ref "CF2.1") (pin "6") (pinfunction "6_6") (pintype "passive"))
      (node (ref "CF3.1") (pin "5") (pinfunction "5_5") (pintype "passive"))
      (node (ref "CF3.1") (pin "6") (pinfunction "6_6") (pintype "passive"))
      (node (ref "CF4.1") (pin "5") (pinfunction "5_5") (pintype "passive"))
      (node (ref "CF4.1") (pin "6") (pinfunction "6_6") (pintype "passive"))
      (node (ref "CF7.1") (pin "5") (pinfunction "5_5") (pintype "passive"))
      (node (ref "CF7.1") (pin "6") (pinfunction "6_6") (pintype "passive"))
      (node (ref "CF8.1") (pin "5") (pinfunction "5_5") (pintype "passive"))
      (node (ref "CF8.1") (pin "6") (pinfunction "6_6") (pintype "passive"))
    )
    (net (code "4") (name "AUX-4") (class "Default")
      (node (ref "CF2.1") (pin "7") (pinfunction "7_7") (pintype "passive"))
      (node (ref "CF2.1") (pin "8") (pinfunction "8_8") (pintype "passive"))
      (node (ref "CF3.1") (pin "7") (pinfunction "7_7") (pintype "passive"))
      (node (ref "CF3.1") (pin "8") (pinfunction "8_8") (pintype "passive"))
      (node (ref "CF4.1") (pin "7") (pinfunction "7_7") (pintype "passive"))
      (node (ref "CF4.1") (pin "8") (pinfunction "8_8") (pintype "passive"))
      (node (ref "CF7.1") (pin "7") (pinfunction "7_7") (pintype "passive"))
      (node (ref "CF7.1") (pin "8") (pinfunction "8_8") (pintype "passive"))
      (node (ref "CF8.1") (pin "7") (pinfunction "7_7") (pintype "passive"))
      (node (ref "CF8.1") (pin "8") (pinfunction "8_8") (pintype "passive"))
    )
    (net (code "5") (name "AUX-5") (class "Default")
      (node (ref "CF2.1") (pin "10") (pinfunction "10_10") (pintype "passive"))
      (node (ref "CF2.1") (pin "9") (pinfunction "9_9") (pintype "passive"))
      (node (ref "CF3.1") (pin "10") (pinfunction "10_10") (pintype "passive"))
      (node (ref "CF3.1") (pin "9") (pinfunction "9_9") (pintype "passive"))
      (node (ref "CF4.1") (pin "10") (pinfunction "10_10") (pintype "passive"))
      (node (ref "CF4.1") (pin "9") (pinfunction "9_9") (pintype "passive"))
      (node (ref "CF7.1") (pin "10") (pinfunction "10_10") (pintype "passive"))
      (node (ref "CF7.1") (pin "9") (pinfunction "9_9") (pintype "passive"))
      (node (ref "CF8.1") (pin "10") (pinfunction "10_10") (pintype "passive"))
      (node (ref "CF8.1") (pin "9") (pinfunction "9_9") (pintype "passive"))
    )
    (net (code "6") (name "AUX-6") (class "Default")
      (node (ref "CF2.1") (pin "11") (pinfunction "11_11") (pintype "passive"))
      (node (ref "CF2.1") (pin "12") (pinfunction "12_12") (pintype "passive"))
      (node (ref "CF3.1") (pin "11") (pinfunction "11_11") (pintype "passive"))
      (node (ref "CF3.1") (pin "12") (pinfunction "12_12") (pintype "passive"))
      (node (ref "CF4.1") (pin "11") (pinfunction "11_11") (pintype "passive"))
      (node (ref "CF4.1") (pin "12") (pinfunction "12_12") (pintype "passive"))
      (node (ref "CF7.1") (pin "11") (pinfunction "11_11") (pintype "passive"))
      (node (ref "CF7.1") (pin "12") (pinfunction "12_12") (pintype "passive"))
      (node (ref "CF8.1") (pin "11") (pinfunction "11_11") (pintype "passive"))
      (node (ref "CF8.1") (pin "12") (pinfunction "12_12") (pintype "passive"))
    )
    (net (code "7") (name "AUX-7") (class "Default")
      (node (ref "CF2.1") (pin "13") (pinfunction "13_13") (pintype "passive"))
      (node (ref "CF2.1") (pin "14") (pinfunction "14_14") (pintype "passive"))
      (node (ref "CF3.1") (pin "13") (pinfunction "13_13") (pintype "passive"))
      (node (ref "CF3.1") (pin "14") (pinfunction "14_14") (pintype "passive"))
      (node (ref "CF4.1") (pin "13") (pinfunction "13_13") (pintype "passive"))
      (node (ref "CF4.1") (pin "14") (pinfunction "14_14") (pintype "passive"))
      (node (ref "CF7.1") (pin "13") (pinfunction "13_13") (pintype "passive"))
      (node (ref "CF7.1") (pin "14") (pinfunction "14_14") (pintype "passive"))
      (node (ref "CF8.1") (pin "13") (pinfunction "13_13") (pintype "passive"))
      (node (ref "CF8.1") (pin "14") (pinfunction "14_14") (pintype "passive"))
    )
    (net (code "8") (name "AUX-8") (class "Default")
      (node (ref "CF2.1") (pin "15") (pinfunction "15_15") (pintype "passive"))
      (node (ref "CF2.1") (pin "16") (pinfunction "16_16") (pintype "passive"))
      (node (ref "CF3.1") (pin "15") (pinfunction "15_15") (pintype "passive"))
      (node (ref "CF3.1") (pin "16") (pinfunction "16_16") (pintype "passive"))
      (node (ref "CF4.1") (pin "15") (pinfunction "15_15") (pintype "passive"))
      (node (ref "CF4.1") (pin "16") (pinfunction "16_16") (pintype "passive"))
      (node (ref "CF7.1") (pin "15") (pinfunction "15_15") (pintype "passive"))
      (node (ref "CF7.1") (pin "16") (pinfunction "16_16") (pintype "passive"))
      (node (ref "CF8.1") (pin "15") (pinfunction "15_15") (pintype "passive"))
      (node (ref "CF8.1") (pin "16") (pinfunction "16_16") (pintype "passive"))
    )
    (net (code "9") (name "AUX-9") (class "Default")
      (node (ref "CF2.1") (pin "17") (pinfunction "17_17") (pintype "passive"))
      (node (ref "CF2.1") (pin "18") (pinfunction "18_18") (pintype "passive"))
      (node (ref "CF3.1") (pin "17") (pinfunction "17_17") (pintype "passive"))
      (node (ref "CF3.1") (pin "18") (pinfunction "18_18") (pintype "passive"))
      (node (ref "CF4.1") (pin "17") (pinfunction "17_17") (pintype "passive"))
      (node (ref "CF4.1") (pin "18") (pinfunction "18_18") (pintype "passive"))
      (node (ref "CF7.1") (pin "17") (pinfunction "17_17") (pintype "passive"))
      (node (ref "CF7.1") (pin "18") (pinfunction "18_18") (pintype "passive"))
      (node (ref "CF8.1") (pin "17") (pinfunction "17_17") (pintype "passive"))
      (node (ref "CF8.1") (pin "18") (pinfunction "18_18") (pintype "passive"))
    )
    (net (code "10") (name "AUX-10") (class "Default")
      (node (ref "CF2.1") (pin "19") (pinfunction "19_19") (pintype "passive"))
      (node (ref "CF2.1") (pin "20") (pinfunction "20_20") (pintype "passive"))
      (node (ref "CF3.1") (pin "19") (pinfunction "19_19") (pintype "passive"))
      (node (ref "CF3.1") (pin "20") (pinfunction "20_20") (pintype "passive"))
      (node (ref "CF4.1") (pin "19") (pinfunction "19_19") (pintype "passive"))
      (node (ref "CF4.1") (pin "20") (pinfunction "20_20") (pintype "passive"))
      (node (ref "CF7.1") (pin "19") (pinfunction "19_19") (pintype "passive"))
      (node (ref "CF7.1") (pin "20") (pinfunction "20_20") (pintype "passive"))
      (node (ref "CF8.1") (pin "19") (pinfunction "19_19") (pintype "passive"))
      (node (ref "CF8.1") (pin "20") (pinfunction "20_20") (pintype "passive"))
    )
    (net (code "11") (name "CAN1_H") (class "Default")
      (node (ref "CF1.2") (pin "33") (pinfunction "33_33") (pintype "passive"))
      (node (ref "CF1.2") (pin "34") (pinfunction "34_34") (pintype "passive"))
      (node (ref "CF2.2") (pin "33") (pinfunction "33_33") (pintype "passive"))
      (node (ref "CF2.2") (pin "34") (pinfunction "34_34") (pintype "passive"))
      (node (ref "CF3.2") (pin "33") (pinfunction "33_33") (pintype "passive"))
      (node (ref "CF3.2") (pin "34") (pinfunction "34_34") (pintype "passive"))
      (node (ref "CF4.2") (pin "33") (pinfunction "33_33") (pintype "passive"))
      (node (ref "CF4.2") (pin "34") (pinfunction "34_34") (pintype "passive"))
      (node (ref "CF5.2") (pin "33") (pinfunction "33_33") (pintype "passive"))
      (node (ref "CF5.2") (pin "34") (pinfunction "34_34") (pintype "passive"))
      (node (ref "CF6.2") (pin "33") (pinfunction "33_33") (pintype "passive"))
      (node (ref "CF6.2") (pin "34") (pinfunction "34_34") (pintype "passive"))
      (node (ref "CF7.2") (pin "33") (pinfunction "33_33") (pintype "passive"))
      (node (ref "CF7.2") (pin "34") (pinfunction "34_34") (pintype "passive"))
      (node (ref "CF8.2") (pin "33") (pinfunction "33_33") (pintype "passive"))
      (node (ref "CF8.2") (pin "34") (pinfunction "34_34") (pintype "passive"))
      (node (ref "J3") (pin "17") (pinfunction "17_17") (pintype "passive"))
      (node (ref "R1") (pin "1") (pinfunction "1_1") (pintype "passive"))
      (node (ref "R10") (pin "1") (pinfunction "1_1") (pintype "passive"))
      (node (ref "R5") (pin "1") (pinfunction "1_1") (pintype "passive"))
    )
    (net (code "12") (name "CAN1_L") (class "Default")
      (node (ref "CF1.2") (pin "35") (pinfunction "35_35") (pintype "passive"))
      (node (ref "CF1.2") (pin "36") (pinfunction "36_36") (pintype "passive"))
      (node (ref "CF2.2") (pin "35") (pinfunction "35_35") (pintype "passive"))
      (node (ref "CF2.2") (pin "36") (pinfunction "36_36") (pintype "passive"))
      (node (ref "CF3.2") (pin "35") (pinfunction "35_35") (pintype "passive"))
      (node (ref "CF3.2") (pin "36") (pinfunction "36_36") (pintype "passive"))
      (node (ref "CF4.2") (pin "35") (pinfunction "35_35") (pintype "passive"))
      (node (ref "CF4.2") (pin "36") (pinfunction "36_36") (pintype "passive"))
      (node (ref "CF5.2") (pin "35") (pinfunction "35_35") (pintype "passive"))
      (node (ref "CF5.2") (pin "36") (pinfunction "36_36") (pintype "passive"))
      (node (ref "CF6.2") (pin "35") (pinfunction "35_35") (pintype "passive"))
      (node (ref "CF6.2") (pin "36") (pinfunction "36_36") (pintype "passive"))
      (node (ref "CF7.2") (pin "35") (pinfunction "35_35") (pintype "passive"))
      (node (ref "CF7.2") (pin "36") (pinfunction "36_36") (pintype "passive"))
      (node (ref "CF8.2") (pin "35") (pinfunction "35_35") (pintype "passive"))
      (node (ref "CF8.2") (pin "36") (pinfunction "36_36") (pintype "passive"))
      (node (ref "J3") (pin "18") (pinfunction "18_18") (pintype "passive"))
      (node (ref "R2") (pin "1") (pinfunction "1_1") (pintype "passive"))
      (node (ref "R6") (pin "1") (pinfunction "1_1") (pintype "passive"))
      (node (ref "R9") (pin "1") (pinfunction "1_1") (pintype "passive"))
    )
    (net (code "13") (name "CAN2_H") (class "Default")
      (node (ref "CF1.2") (pin "17") (pinfunction "17_17") (pintype "passive"))
      (node (ref "CF1.2") (pin "18") (pinfunction "18_18") (pintype "passive"))
      (node (ref "CF2.2") (pin "17") (pinfunction "17_17") (pintype "passive"))
      (node (ref "CF2.2") (pin "18") (pinfunction "18_18") (pintype "passive"))
      (node (ref "CF3.2") (pin "17") (pinfunction "17_17") (pintype "passive"))
      (node (ref "CF3.2") (pin "18") (pinfunction "18_18") (pintype "passive"))
      (node (ref "CF4.2") (pin "17") (pinfunction "17_17") (pintype "passive"))
      (node (ref "CF4.2") (pin "18") (pinfunction "18_18") (pintype "passive"))
      (node (ref "CF5.2") (pin "17") (pinfunction "17_17") (pintype "passive"))
      (node (ref "CF5.2") (pin "18") (pinfunction "18_18") (pintype "passive"))
      (node (ref "CF6.2") (pin "17") (pinfunction "17_17") (pintype "passive"))
      (node (ref "CF6.2") (pin "18") (pinfunction "18_18") (pintype "passive"))
      (node (ref "CF7.2") (pin "17") (pinfunction "17_17") (pintype "passive"))
      (node (ref "CF7.2") (pin "18") (pinfunction "18_18") (pintype "passive"))
      (node (ref "CF8.2") (pin "17") (pinfunction "17_17") (pintype "passive"))
      (node (ref "CF8.2") (pin "18") (pinfunction "18_18") (pintype "passive"))
      (node (ref "J3") (pin "9") (pinfunction "9_9") (pintype "passive"))
      (node (ref "R10") (pin "2") (pinfunction "2_2") (pintype "passive"))
      (node (ref "R3") (pin "1") (pinfunction "1_1") (pintype "passive"))
      (node (ref "R7") (pin "1") (pinfunction "1_1") (pintype "passive"))
    )
    (net (code "14") (name "CAN2_L") (class "Default")
      (node (ref "CF1.2") (pin "19") (pinfunction "19_19") (pintype "passive"))
      (node (ref "CF1.2") (pin "20") (pinfunction "20_20") (pintype "passive"))
      (node (ref "CF2.2") (pin "19") (pinfunction "19_19") (pintype "passive"))
      (node (ref "CF2.2") (pin "20") (pinfunction "20_20") (pintype "passive"))
      (node (ref "CF3.2") (pin "19") (pinfunction "19_19") (pintype "passive"))
      (node (ref "CF3.2") (pin "20") (pinfunction "20_20") (pintype "passive"))
      (node (ref "CF4.2") (pin "19") (pinfunction "19_19") (pintype "passive"))
      (node (ref "CF4.2") (pin "20") (pinfunction "20_20") (pintype "passive"))
      (node (ref "CF5.2") (pin "19") (pinfunction "19_19") (pintype "passive"))
      (node (ref "CF5.2") (pin "20") (pinfunction "20_20") (pintype "passive"))
      (node (ref "CF6.2") (pin "19") (pinfunction "19_19") (pintype "passive"))
      (node (ref "CF6.2") (pin "20") (pinfunction "20_20") (pintype "passive"))
      (node (ref "CF7.2") (pin "19") (pinfunction "19_19") (pintype "passive"))
      (node (ref "CF7.2") (pin "20") (pinfunction "20_20") (pintype "passive"))
      (node (ref "CF8.2") (pin "19") (pinfunction "19_19") (pintype "passive"))
      (node (ref "CF8.2") (pin "20") (pinfunction "20_20") (pintype "passive"))
      (node (ref "J3") (pin "10") (pinfunction "10_10") (pintype "passive"))
      (node (ref "R4") (pin "1") (pinfunction "1_1") (pintype "passive"))
      (node (ref "R8") (pin "1") (pinfunction "1_1") (pintype "passive"))
      (node (ref "R9") (pin "2") (pinfunction "2_2") (pintype "passive"))
    )
    (net (code "15") (name "GND") (class "Default")
      (node (ref "C1") (pin "2") (pinfunction "2_2") (pintype "passive"))
      (node (ref "C10") (pin "2") (pinfunction "2_2") (pintype "passive"))
      (node (ref "C11") (pin "2") (pinfunction "2_2") (pintype "passive"))
      (node (ref "C12") (pin "2") (pinfunction "2_2") (pintype "passive"))
      (node (ref "C2") (pin "2") (pinfunction "2_2") (pintype "passive"))
      (node (ref "C3") (pin "2") (pinfunction "2_2") (pintype "passive"))
      (node (ref "C4") (pin "2") (pinfunction "2_2") (pintype "passive"))
      (node (ref "C5") (pin "2") (pinfunction "2_2") (pintype "passive"))
      (node (ref "C6") (pin "2") (pinfunction "2_2") (pintype "passive"))
      (node (ref "C7") (pin "2") (pinfunction "2_2") (pintype "passive"))
      (node (ref "C8") (pin "2") (pinfunction "2_2") (pintype "passive"))
      (node (ref "C9") (pin "2") (pinfunction "2_2") (pintype "passive"))
      (node (ref "CF1.2") (pin "27") (pinfunction "27_27") (pintype "passive"))
      (node (ref "CF1.2") (pin "28") (pinfunction "28_28") (pintype "passive"))
      (node (ref "CF1.2") (pin "29") (pinfunction "29_29") (pintype "passive"))
      (node (ref "CF1.2") (pin "30") (pinfunction "30_30") (pintype "passive"))
      (node (ref "CF1.2") (pin "LC1") (pinfunction "LC1_LC1") (pintype "passive"))
      (node (ref "CF1.2") (pin "LC2") (pinfunction "LC2_LC2") (pintype "passive"))
      (node (ref "CF2.1") (pin "LC1") (pinfunction "LC1_LC1") (pintype "passive"))
      (node (ref "CF2.1") (pin "LC2") (pinfunction "LC2_LC2") (pintype "passive"))
      (node (ref "CF2.2") (pin "27") (pinfunction "27_27") (pintype "passive"))
      (node (ref "CF2.2") (pin "28") (pinfunction "28_28") (pintype "passive"))
      (node (ref "CF2.2") (pin "29") (pinfunction "29_29") (pintype "passive"))
      (node (ref "CF2.2") (pin "30") (pinfunction "30_30") (pintype "passive"))
      (node (ref "CF2.2") (pin "LC1") (pinfunction "LC1_LC1") (pintype "passive"))
      (node (ref "CF2.2") (pin "LC2") (pinfunction "LC2_LC2") (pintype "passive"))
      (node (ref "CF3.1") (pin "LC1") (pinfunction "LC1_LC1") (pintype "passive"))
      (node (ref "CF3.1") (pin "LC2") (pinfunction "LC2_LC2") (pintype "passive"))
      (node (ref "CF3.2") (pin "27") (pinfunction "27_27") (pintype "passive"))
      (node (ref "CF3.2") (pin "28") (pinfunction "28_28") (pintype "passive"))
      (node (ref "CF3.2") (pin "29") (pinfunction "29_29") (pintype "passive"))
      (node (ref "CF3.2") (pin "30") (pinfunction "30_30") (pintype "passive"))
      (node (ref "CF3.2") (pin "LC1") (pinfunction "LC1_LC1") (pintype "passive"))
      (node (ref "CF3.2") (pin "LC2") (pinfunction "LC2_LC2") (pintype "passive"))
      (node (ref "CF4.1") (pin "LC1") (pinfunction "LC1_LC1") (pintype "passive"))
      (node (ref "CF4.1") (pin "LC2") (pinfunction "LC2_LC2") (pintype "passive"))
      (node (ref "CF4.2") (pin "27") (pinfunction "27_27") (pintype "passive"))
      (node (ref "CF4.2") (pin "28") (pinfunction "28_28") (pintype "passive"))
      (node (ref "CF4.2") (pin "29") (pinfunction "29_29") (pintype "passive"))
      (node (ref "CF4.2") (pin "30") (pinfunction "30_30") (pintype "passive"))
      (node (ref "CF4.2") (pin "LC1") (pinfunction "LC1_LC1") (pintype "passive"))
      (node (ref "CF4.2") (pin "LC2") (pinfunction "LC2_LC2") (pintype "passive"))
      (node (ref "CF5.2") (pin "27") (pinfunction "27_27") (pintype "passive"))
      (node (ref "CF5.2") (pin "28") (pinfunction "28_28") (pintype "passive"))
      (node (ref "CF5.2") (pin "29") (pinfunction "29_29") (pintype "passive"))
      (node (ref "CF5.2") (pin "30") (pinfunction "30_30") (pintype "passive"))
      (node (ref "CF5.2") (pin "LC1") (pinfunction "LC1_LC1") (pintype "passive"))
      (node (ref "CF5.2") (pin "LC2") (pinfunction "LC2_LC2") (pintype "passive"))
      (node (ref "CF6.2") (pin "27") (pinfunction "27_27") (pintype "passive"))
      (node (ref "CF6.2") (pin "28") (pinfunction "28_28") (pintype "passive"))
      (node (ref "CF6.2") (pin "29") (pinfunction "29_29") (pintype "passive"))
      (node (ref "CF6.2") (pin "30") (pinfunction "30_30") (pintype "passive"))
      (node (ref "CF6.2") (pin "LC1") (pinfunction "LC1_LC1") (pintype "passive"))
      (node (ref "CF6.2") (pin "LC2") (pinfunction "LC2_LC2") (pintype "passive"))
      (node (ref "CF7.1") (pin "LC1") (pinfunction "LC1_LC1") (pintype "passive"))
      (node (ref "CF7.1") (pin "LC2") (pinfunction "LC2_LC2") (pintype "passive"))
      (node (ref "CF7.2") (pin "27") (pinfunction "27_27") (pintype "passive"))
      (node (ref "CF7.2") (pin "28") (pinfunction "28_28") (pintype "passive"))
      (node (ref "CF7.2") (pin "29") (pinfunction "29_29") (pintype "passive"))
      (node (ref "CF7.2") (pin "30") (pinfunction "30_30") (pintype "passive"))
      (node (ref "CF7.2") (pin "LC1") (pinfunction "LC1_LC1") (pintype "passive"))
      (node (ref "CF7.2") (pin "LC2") (pinfunction "LC2_LC2") (pintype "passive"))
      (node (ref "CF8.1") (pin "LC1") (pinfunction "LC1_LC1") (pintype "passive"))
      (node (ref "CF8.1") (pin "LC2") (pinfunction "LC2_LC2") (pintype "passive"))
      (node (ref "CF8.2") (pin "27") (pinfunction "27_27") (pintype "passive"))
      (node (ref "CF8.2") (pin "28") (pinfunction "28_28") (pintype "passive"))
      (node (ref "CF8.2") (pin "29") (pinfunction "29_29") (pintype "passive"))
      (node (ref "CF8.2") (pin "30") (pinfunction "30_30") (pintype "passive"))
      (node (ref "CF8.2") (pin "LC1") (pinfunction "LC1_LC1") (pintype "passive"))
      (node (ref "CF8.2") (pin "LC2") (pinfunction "LC2_LC2") (pintype "passive"))
      (node (ref "CM1.1") (pin "P$1") (pinfunction "SHIELD1_P$1") (pintype "passive"))
      (node (ref "CM1.1") (pin "P$2") (pinfunction "SHIELD1_P$2") (pintype "passive"))
      (node (ref "CM1.1") (pin "P$3") (pinfunction "SHIELD1_P$3") (pintype "passive"))
      (node (ref "CM1.1") (pin "P$4") (pinfunction "SHIELD1_P$4") (pintype "passive"))
      (node (ref "CM1.2") (pin "P$1") (pinfunction "SHIELD1_P$1") (pintype "passive"))
      (node (ref "CM1.2") (pin "P$2") (pinfunction "SHIELD1_P$2") (pintype "passive"))
      (node (ref "CM1.2") (pin "P$3") (pinfunction "SHIELD1_P$3") (pintype "passive"))
      (node (ref "CM1.2") (pin "P$4") (pinfunction "SHIELD1_P$4") (pintype "passive"))
      (node (ref "CM1.3") (pin "P$1") (pinfunction "SHIELD1_P$1") (pintype "passive"))
      (node (ref "CM1.3") (pin "P$2") (pinfunction "SHIELD1_P$2") (pintype "passive"))
      (node (ref "CM1.3") (pin "P$3") (pinfunction "SHIELD1_P$3") (pintype "passive"))
      (node (ref "CM1.3") (pin "P$4") (pinfunction "SHIELD1_P$4") (pintype "passive"))
      (node (ref "CM2.2") (pin "P$1") (pinfunction "SHIELD1_P$1") (pintype "passive"))
      (node (ref "CM2.2") (pin "P$2") (pinfunction "SHIELD1_P$2") (pintype "passive"))
      (node (ref "CM2.2") (pin "P$3") (pinfunction "SHIELD1_P$3") (pintype "passive"))
      (node (ref "CM2.2") (pin "P$4") (pinfunction "SHIELD1_P$4") (pintype "passive"))
      (node (ref "CM2.3") (pin "P$1") (pinfunction "SHIELD1_P$1") (pintype "passive"))
      (node (ref "CM2.3") (pin "P$2") (pinfunction "SHIELD1_P$2") (pintype "passive"))
      (node (ref "CM2.3") (pin "P$3") (pinfunction "SHIELD1_P$3") (pintype "passive"))
      (node (ref "CM2.3") (pin "P$4") (pinfunction "SHIELD1_P$4") (pintype "passive"))
      (node (ref "CM3.2") (pin "P$1") (pinfunction "SHIELD1_P$1") (pintype "passive"))
      (node (ref "CM3.2") (pin "P$2") (pinfunction "SHIELD1_P$2") (pintype "passive"))
      (node (ref "CM3.2") (pin "P$3") (pinfunction "SHIELD1_P$3") (pintype "passive"))
      (node (ref "CM3.2") (pin "P$4") (pinfunction "SHIELD1_P$4") (pintype "passive"))
      (node (ref "CM4.1") (pin "P$1") (pinfunction "SHIELD1_P$1") (pintype "passive"))
      (node (ref "CM4.1") (pin "P$2") (pinfunction "SHIELD1_P$2") (pintype "passive"))
      (node (ref "CM4.1") (pin "P$3") (pinfunction "SHIELD1_P$3") (pintype "passive"))
      (node (ref "CM4.1") (pin "P$4") (pinfunction "SHIELD1_P$4") (pintype "passive"))
      (node (ref "CM8") (pin "2") (pinfunction "P$2_2") (pintype "bidirectional"))
      (node (ref "CM8") (pin "3") (pinfunction "P$2_3") (pintype "bidirectional"))
      (node (ref "J1") (pin "HD1") (pinfunction "HD_HD1") (pintype "passive"))
      (node (ref "J1") (pin "HD2") (pinfunction "HD_HD2") (pintype "passive"))
      (node (ref "J1") (pin "HD3") (pinfunction "HD_HD3") (pintype "passive"))
      (node (ref "J3") (pin "14") (pinfunction "14_14") (pintype "passive"))
      (node (ref "J3") (pin "15") (pinfunction "15_15") (pintype "passive"))
      (node (ref "J3") (pin "16") (pinfunction "16_16") (pintype "passive"))
      (node (ref "J3") (pin "19") (pinfunction "19_19") (pintype "passive"))
    )
    (net (code "16") (name "L-TURNSTILE") (class "Default")
      (node (ref "CM1.2") (pin "RF-DOWN") (pinfunction "RF_RF-DOWN") (pintype "passive"))
      (node (ref "CM2.2") (pin "RF-DOWN") (pinfunction "RF_RF-DOWN") (pintype "passive"))
    )
    (net (code "17") (name "L1-TURNSTILE") (class "Default")
      (node (ref "CM1.1") (pin "RF-DOWN") (pinfunction "RF_RF-DOWN") (pintype "passive"))
      (node (ref "CM3.2") (pin "RF-DOWN") (pinfunction "RF_RF-DOWN") (pintype "passive"))
    )
    (net (code "18") (name "Net-(C1-Pad1)") (class "Default")
      (node (ref "C1") (pin "1") (pinfunction "1_1") (pintype "passive"))
      (node (ref "R1") (pin "2") (pinfunction "2_2") (pintype "passive"))
      (node (ref "R2") (pin "2") (pinfunction "2_2") (pintype "passive"))
    )
    (net (code "19") (name "Net-(C2-Pad1)") (class "Default")
      (node (ref "C2") (pin "1") (pinfunction "1_1") (pintype "passive"))
      (node (ref "R3") (pin "2") (pinfunction "2_2") (pintype "passive"))
      (node (ref "R4") (pin "2") (pinfunction "2_2") (pintype "passive"))
    )
    (net (code "20") (name "Net-(C3-Pad1)") (class "Default")
      (node (ref "C3") (pin "1") (pinfunction "1_1") (pintype "passive"))
      (node (ref "R5") (pin "2") (pinfunction "2_2") (pintype "passive"))
      (node (ref "R6") (pin "2") (pinfunction "2_2") (pintype "passive"))
    )
    (net (code "21") (name "Net-(C4-Pad1)") (class "Default")
      (node (ref "C4") (pin "1") (pinfunction "1_1") (pintype "passive"))
      (node (ref "R7") (pin "2") (pinfunction "2_2") (pintype "passive"))
      (node (ref "R8") (pin "2") (pinfunction "2_2") (pintype "passive"))
    )
    (net (code "22") (name "OPD_PWR") (class "Default")
      (node (ref "CF1.2") (pin "15") (pinfunction "15_15") (pintype "passive"))
      (node (ref "CF1.2") (pin "16") (pinfunction "16_16") (pintype "passive"))
      (node (ref "CF2.2") (pin "15") (pinfunction "15_15") (pintype "passive"))
      (node (ref "CF2.2") (pin "16") (pinfunction "16_16") (pintype "passive"))
      (node (ref "CF3.2") (pin "15") (pinfunction "15_15") (pintype "passive"))
      (node (ref "CF3.2") (pin "16") (pinfunction "16_16") (pintype "passive"))
      (node (ref "CF4.2") (pin "15") (pinfunction "15_15") (pintype "passive"))
      (node (ref "CF4.2") (pin "16") (pinfunction "16_16") (pintype "passive"))
      (node (ref "CF5.2") (pin "15") (pinfunction "15_15") (pintype "passive"))
      (node (ref "CF5.2") (pin "16") (pinfunction "16_16") (pintype "passive"))
      (node (ref "CF6.2") (pin "15") (pinfunction "15_15") (pintype "passive"))
      (node (ref "CF6.2") (pin "16") (pinfunction "16_16") (pintype "passive"))
      (node (ref "CF7.2") (pin "15") (pinfunction "15_15") (pintype "passive"))
      (node (ref "CF7.2") (pin "16") (pinfunction "16_16") (pintype "passive"))
      (node (ref "CF8.2") (pin "15") (pinfunction "15_15") (pintype "passive"))
      (node (ref "CF8.2") (pin "16") (pinfunction "16_16") (pintype "passive"))
      (node (ref "J3") (pin "8") (pinfunction "8_8") (pintype "passive"))
    )
    (net (code "23") (name "OPD_SCL") (class "Default")
      (node (ref "CF1.2") (pin "13") (pinfunction "13_13") (pintype "passive"))
      (node (ref "CF1.2") (pin "14") (pinfunction "14_14") (pintype "passive"))
      (node (ref "CF2.2") (pin "13") (pinfunction "13_13") (pintype "passive"))
      (node (ref "CF2.2") (pin "14") (pinfunction "14_14") (pintype "passive"))
      (node (ref "CF3.2") (pin "13") (pinfunction "13_13") (pintype "passive"))
      (node (ref "CF3.2") (pin "14") (pinfunction "14_14") (pintype "passive"))
      (node (ref "CF4.2") (pin "13") (pinfunction "13_13") (pintype "passive"))
      (node (ref "CF4.2") (pin "14") (pinfunction "14_14") (pintype "passive"))
      (node (ref "CF5.2") (pin "13") (pinfunction "13_13") (pintype "passive"))
      (node (ref "CF5.2") (pin "14") (pinfunction "14_14") (pintype "passive"))
      (node (ref "CF6.2") (pin "13") (pinfunction "13_13") (pintype "passive"))
      (node (ref "CF6.2") (pin "14") (pinfunction "14_14") (pintype "passive"))
      (node (ref "CF7.2") (pin "13") (pinfunction "13_13") (pintype "passive"))
      (node (ref "CF7.2") (pin "14") (pinfunction "14_14") (pintype "passive"))
      (node (ref "CF8.2") (pin "13") (pinfunction "13_13") (pintype "passive"))
      (node (ref "CF8.2") (pin "14") (pinfunction "14_14") (pintype "passive"))
      (node (ref "J3") (pin "7") (pinfunction "7_7") (pintype "passive"))
    )
    (net (code "24") (name "OPD_SDA") (class "Default")
      (node (ref "CF1.2") (pin "11") (pinfunction "11_11") (pintype "passive"))
      (node (ref "CF1.2") (pin "12") (pinfunction "12_12") (pintype "passive"))
      (node (ref "CF2.2") (pin "11") (pinfunction "11_11") (pintype "passive"))
      (node (ref "CF2.2") (pin "12") (pinfunction "12_12") (pintype "passive"))
      (node (ref "CF3.2") (pin "11") (pinfunction "11_11") (pintype "passive"))
      (node (ref "CF3.2") (pin "12") (pinfunction "12_12") (pintype "passive"))
      (node (ref "CF4.2") (pin "11") (pinfunction "11_11") (pintype "passive"))
      (node (ref "CF4.2") (pin "12") (pinfunction "12_12") (pintype "passive"))
      (node (ref "CF5.2") (pin "11") (pinfunction "11_11") (pintype "passive"))
      (node (ref "CF5.2") (pin "12") (pinfunction "12_12") (pintype "passive"))
      (node (ref "CF6.2") (pin "11") (pinfunction "11_11") (pintype "passive"))
      (node (ref "CF6.2") (pin "12") (pinfunction "12_12") (pintype "passive"))
      (node (ref "CF7.2") (pin "11") (pinfunction "11_11") (pintype "passive"))
      (node (ref "CF7.2") (pin "12") (pinfunction "12_12") (pintype "passive"))
      (node (ref "CF8.2") (pin "11") (pinfunction "11_11") (pintype "passive"))
      (node (ref "CF8.2") (pin "12") (pinfunction "12_12") (pintype "passive"))
      (node (ref "J3") (pin "6") (pinfunction "6_6") (pintype "passive"))
    )
    (net (code "25") (name "S-PATCH") (class "Default")
      (node (ref "CM4.1") (pin "RF-DOWN") (pinfunction "RF_RF-DOWN") (pintype "passive"))
      (node (ref "CM8") (pin "1") (pinfunction "P$1_1") (pintype "bidirectional"))
    )
    (net (code "26") (name "SPARE1") (class "Default")
      (node (ref "CF1.2") (pin "1") (pinfunction "1_1") (pintype "passive"))
      (node (ref "CF1.2") (pin "2") (pinfunction "2_2") (pintype "passive"))
      (node (ref "CF2.2") (pin "1") (pinfunction "1_1") (pintype "passive"))
      (node (ref "CF2.2") (pin "2") (pinfunction "2_2") (pintype "passive"))
      (node (ref "CF3.2") (pin "1") (pinfunction "1_1") (pintype "passive"))
      (node (ref "CF3.2") (pin "2") (pinfunction "2_2") (pintype "passive"))
      (node (ref "CF4.2") (pin "1") (pinfunction "1_1") (pintype "passive"))
      (node (ref "CF4.2") (pin "2") (pinfunction "2_2") (pintype "passive"))
      (node (ref "CF5.2") (pin "1") (pinfunction "1_1") (pintype "passive"))
      (node (ref "CF5.2") (pin "2") (pinfunction "2_2") (pintype "passive"))
      (node (ref "CF6.2") (pin "1") (pinfunction "1_1") (pintype "passive"))
      (node (ref "CF6.2") (pin "2") (pinfunction "2_2") (pintype "passive"))
      (node (ref "CF7.2") (pin "1") (pinfunction "1_1") (pintype "passive"))
      (node (ref "CF7.2") (pin "2") (pinfunction "2_2") (pintype "passive"))
      (node (ref "CF8.2") (pin "1") (pinfunction "1_1") (pintype "passive"))
      (node (ref "CF8.2") (pin "2") (pinfunction "2_2") (pintype "passive"))
      (node (ref "J1") (pin "19") (pinfunction "19_19") (pintype "passive"))
      (node (ref "J1") (pin "20") (pinfunction "20_20") (pintype "passive"))
    )
    (net (code "27") (name "SPARE1-TURNSTILE-DPLY") (class "Default")
      (node (ref "J3") (pin "5") (pinfunction "5_5") (pintype "passive"))
    )
    (net (code "28") (name "SPARE2") (class "Default")
      (node (ref "J3") (pin "4") (pinfunction "4_4") (pintype "passive"))
    )
    (net (code "29") (name "SPARE3") (class "Default")
      (node (ref "CF1.2") (pin "3") (pinfunction "3_3") (pintype "passive"))
      (node (ref "CF2.2") (pin "3") (pinfunction "3_3") (pintype "passive"))
      (node (ref "CF3.2") (pin "3") (pinfunction "3_3") (pintype "passive"))
      (node (ref "CF4.2") (pin "3") (pinfunction "3_3") (pintype "passive"))
      (node (ref "CF5.2") (pin "3") (pinfunction "3_3") (pintype "passive"))
      (node (ref "CF6.2") (pin "3") (pinfunction "3_3") (pintype "passive"))
      (node (ref "CF7.2") (pin "3") (pinfunction "3_3") (pintype "passive"))
      (node (ref "CF8.2") (pin "3") (pinfunction "3_3") (pintype "passive"))
      (node (ref "J1") (pin "18") (pinfunction "18_18") (pintype "passive"))
    )
    (net (code "30") (name "SPARE3-MAG-PWR") (class "Default")
      (node (ref "J3") (pin "3") (pinfunction "3_3") (pintype "passive"))
    )
    (net (code "31") (name "SPARE4") (class "Default")
      (node (ref "CF1.2") (pin "4") (pinfunction "4_4") (pintype "passive"))
      (node (ref "CF2.2") (pin "4") (pinfunction "4_4") (pintype "passive"))
      (node (ref "CF3.2") (pin "4") (pinfunction "4_4") (pintype "passive"))
      (node (ref "CF4.2") (pin "4") (pinfunction "4_4") (pintype "passive"))
      (node (ref "CF5.2") (pin "4") (pinfunction "4_4") (pintype "passive"))
      (node (ref "CF6.2") (pin "4") (pinfunction "4_4") (pintype "passive"))
      (node (ref "CF7.2") (pin "4") (pinfunction "4_4") (pintype "passive"))
      (node (ref "CF8.2") (pin "4") (pinfunction "4_4") (pintype "passive"))
      (node (ref "J1") (pin "17") (pinfunction "17_17") (pintype "passive"))
    )
    (net (code "32") (name "SPARE4-MAG-SCL") (class "Default")
      (node (ref "J3") (pin "2") (pinfunction "2_2") (pintype "passive"))
    )
    (net (code "33") (name "SPARE5") (class "Default")
      (node (ref "CF1.2") (pin "5") (pinfunction "5_5") (pintype "passive"))
      (node (ref "CF2.2") (pin "5") (pinfunction "5_5") (pintype "passive"))
      (node (ref "CF3.2") (pin "5") (pinfunction "5_5") (pintype "passive"))
      (node (ref "CF4.2") (pin "5") (pinfunction "5_5") (pintype "passive"))
      (node (ref "CF5.2") (pin "5") (pinfunction "5_5") (pintype "passive"))
      (node (ref "CF6.2") (pin "5") (pinfunction "5_5") (pintype "passive"))
      (node (ref "CF7.2") (pin "5") (pinfunction "5_5") (pintype "passive"))
      (node (ref "CF8.2") (pin "5") (pinfunction "5_5") (pintype "passive"))
      (node (ref "J1") (pin "16") (pinfunction "16_16") (pintype "passive"))
    )
    (net (code "34") (name "SPARE5-MAG-SDA") (class "Default")
      (node (ref "J3") (pin "1") (pinfunction "1_1") (pintype "passive"))
    )
    (net (code "35") (name "SPARE6") (class "Default")
      (node (ref "CF1.2") (pin "6") (pinfunction "6_6") (pintype "passive"))
      (node (ref "CF2.2") (pin "6") (pinfunction "6_6") (pintype "passive"))
      (node (ref "CF3.2") (pin "6") (pinfunction "6_6") (pintype "passive"))
      (node (ref "CF4.2") (pin "6") (pinfunction "6_6") (pintype "passive"))
      (node (ref "CF5.2") (pin "6") (pinfunction "6_6") (pintype "passive"))
      (node (ref "CF6.2") (pin "6") (pinfunction "6_6") (pintype "passive"))
      (node (ref "CF7.2") (pin "6") (pinfunction "6_6") (pintype "passive"))
      (node (ref "CF8.2") (pin "6") (pinfunction "6_6") (pintype "passive"))
      (node (ref "J1") (pin "15") (pinfunction "15_15") (pintype "passive"))
    )
    (net (code "36") (name "SPARE7") (class "Default")
      (node (ref "CF1.2") (pin "7") (pinfunction "7_7") (pintype "passive"))
      (node (ref "CF2.2") (pin "7") (pinfunction "7_7") (pintype "passive"))
      (node (ref "CF3.2") (pin "7") (pinfunction "7_7") (pintype "passive"))
      (node (ref "CF4.2") (pin "7") (pinfunction "7_7") (pintype "passive"))
      (node (ref "CF5.2") (pin "7") (pinfunction "7_7") (pintype "passive"))
      (node (ref "CF6.2") (pin "7") (pinfunction "7_7") (pintype "passive"))
      (node (ref "CF7.2") (pin "7") (pinfunction "7_7") (pintype "passive"))
      (node (ref "CF8.2") (pin "7") (pinfunction "7_7") (pintype "passive"))
      (node (ref "J1") (pin "14") (pinfunction "14_14") (pintype "passive"))
    )
    (net (code "37") (name "SPARE8") (class "Default")
      (node (ref "CF1.2") (pin "8") (pinfunction "8_8") (pintype "passive"))
      (node (ref "CF2.2") (pin "8") (pinfunction "8_8") (pintype "passive"))
      (node (ref "CF3.2") (pin "8") (pinfunction "8_8") (pintype "passive"))
      (node (ref "CF4.2") (pin "8") (pinfunction "8_8") (pintype "passive"))
      (node (ref "CF5.2") (pin "8") (pinfunction "8_8") (pintype "passive"))
      (node (ref "CF6.2") (pin "8") (pinfunction "8_8") (pintype "passive"))
      (node (ref "CF7.2") (pin "8") (pinfunction "8_8") (pintype "passive"))
      (node (ref "CF8.2") (pin "8") (pinfunction "8_8") (pintype "passive"))
      (node (ref "J1") (pin "13") (pinfunction "13_13") (pintype "passive"))
    )
    (net (code "38") (name "SPARE9") (class "Default")
      (node (ref "CF1.2") (pin "9") (pinfunction "9_9") (pintype "passive"))
      (node (ref "CF2.2") (pin "9") (pinfunction "9_9") (pintype "passive"))
      (node (ref "CF3.2") (pin "9") (pinfunction "9_9") (pintype "passive"))
      (node (ref "CF4.2") (pin "9") (pinfunction "9_9") (pintype "passive"))
      (node (ref "CF5.2") (pin "9") (pinfunction "9_9") (pintype "passive"))
      (node (ref "CF6.2") (pin "9") (pinfunction "9_9") (pintype "passive"))
      (node (ref "CF7.2") (pin "9") (pinfunction "9_9") (pintype "passive"))
      (node (ref "CF8.2") (pin "9") (pinfunction "9_9") (pintype "passive"))
      (node (ref "J1") (pin "12") (pinfunction "12_12") (pintype "passive"))
    )
    (net (code "39") (name "SPARE10") (class "Default")
      (node (ref "CF1.2") (pin "10") (pinfunction "10_10") (pintype "passive"))
      (node (ref "CF2.2") (pin "10") (pinfunction "10_10") (pintype "passive"))
      (node (ref "CF3.2") (pin "10") (pinfunction "10_10") (pintype "passive"))
      (node (ref "CF4.2") (pin "10") (pinfunction "10_10") (pintype "passive"))
      (node (ref "CF5.2") (pin "10") (pinfunction "10_10") (pintype "passive"))
      (node (ref "CF6.2") (pin "10") (pinfunction "10_10") (pintype "passive"))
      (node (ref "CF7.2") (pin "10") (pinfunction "10_10") (pintype "passive"))
      (node (ref "CF8.2") (pin "10") (pinfunction "10_10") (pintype "passive"))
      (node (ref "J1") (pin "11") (pinfunction "11_11") (pintype "passive"))
    )
    (net (code "40") (name "SPARE21") (class "Default")
      (node (ref "CF1.2") (pin "21") (pinfunction "21_21") (pintype "passive"))
      (node (ref "CF2.2") (pin "21") (pinfunction "21_21") (pintype "passive"))
      (node (ref "CF3.2") (pin "21") (pinfunction "21_21") (pintype "passive"))
      (node (ref "CF4.2") (pin "21") (pinfunction "21_21") (pintype "passive"))
      (node (ref "CF5.2") (pin "21") (pinfunction "21_21") (pintype "passive"))
      (node (ref "CF6.2") (pin "21") (pinfunction "21_21") (pintype "passive"))
      (node (ref "CF7.2") (pin "21") (pinfunction "21_21") (pintype "passive"))
      (node (ref "CF8.2") (pin "21") (pinfunction "21_21") (pintype "passive"))
    )
    (net (code "41") (name "SPARE22") (class "Default")
      (node (ref "CF1.2") (pin "22") (pinfunction "22_22") (pintype "passive"))
      (node (ref "CF2.2") (pin "22") (pinfunction "22_22") (pintype "passive"))
      (node (ref "CF3.2") (pin "22") (pinfunction "22_22") (pintype "passive"))
      (node (ref "CF4.2") (pin "22") (pinfunction "22_22") (pintype "passive"))
      (node (ref "CF5.2") (pin "22") (pinfunction "22_22") (pintype "passive"))
      (node (ref "CF6.2") (pin "22") (pinfunction "22_22") (pintype "passive"))
      (node (ref "CF7.2") (pin "22") (pinfunction "22_22") (pintype "passive"))
      (node (ref "CF8.2") (pin "22") (pinfunction "22_22") (pintype "passive"))
    )
    (net (code "42") (name "SPARE31") (class "Default")
      (node (ref "CF1.2") (pin "31") (pinfunction "31_31") (pintype "passive"))
      (node (ref "CF2.2") (pin "31") (pinfunction "31_31") (pintype "passive"))
      (node (ref "CF3.2") (pin "31") (pinfunction "31_31") (pintype "passive"))
      (node (ref "CF4.2") (pin "31") (pinfunction "31_31") (pintype "passive"))
      (node (ref "CF5.2") (pin "31") (pinfunction "31_31") (pintype "passive"))
      (node (ref "CF6.2") (pin "31") (pinfunction "31_31") (pintype "passive"))
      (node (ref "CF7.2") (pin "31") (pinfunction "31_31") (pintype "passive"))
      (node (ref "CF8.2") (pin "31") (pinfunction "31_31") (pintype "passive"))
    )
    (net (code "43") (name "SPARE32") (class "Default")
      (node (ref "CF1.2") (pin "32") (pinfunction "32_32") (pintype "passive"))
      (node (ref "CF2.2") (pin "32") (pinfunction "32_32") (pintype "passive"))
      (node (ref "CF3.2") (pin "32") (pinfunction "32_32") (pintype "passive"))
      (node (ref "CF4.2") (pin "32") (pinfunction "32_32") (pintype "passive"))
      (node (ref "CF5.2") (pin "32") (pinfunction "32_32") (pintype "passive"))
      (node (ref "CF6.2") (pin "32") (pinfunction "32_32") (pintype "passive"))
      (node (ref "CF7.2") (pin "32") (pinfunction "32_32") (pintype "passive"))
      (node (ref "CF8.2") (pin "32") (pinfunction "32_32") (pintype "passive"))
    )
    (net (code "44") (name "UART-RX") (class "Default")
      (node (ref "CF1.2") (pin "38") (pinfunction "38_38") (pintype "passive"))
      (node (ref "CF2.2") (pin "38") (pinfunction "38_38") (pintype "passive"))
      (node (ref "CF3.2") (pin "38") (pinfunction "38_38") (pintype "passive"))
      (node (ref "CF4.2") (pin "38") (pinfunction "38_38") (pintype "passive"))
      (node (ref "CF5.2") (pin "38") (pinfunction "38_38") (pintype "passive"))
      (node (ref "CF6.2") (pin "38") (pinfunction "38_38") (pintype "passive"))
      (node (ref "CF7.2") (pin "38") (pinfunction "38_38") (pintype "passive"))
      (node (ref "CF8.2") (pin "38") (pinfunction "38_38") (pintype "passive"))
    )
    (net (code "45") (name "UART-TX") (class "Default")
      (node (ref "CF1.2") (pin "37") (pinfunction "37_37") (pintype "passive"))
      (node (ref "CF2.2") (pin "37") (pinfunction "37_37") (pintype "passive"))
      (node (ref "CF3.2") (pin "37") (pinfunction "37_37") (pintype "passive"))
      (node (ref "CF4.2") (pin "37") (pinfunction "37_37") (pintype "passive"))
      (node (ref "CF5.2") (pin "37") (pinfunction "37_37") (pintype "passive"))
      (node (ref "CF6.2") (pin "37") (pinfunction "37_37") (pintype "passive"))
      (node (ref "CF7.2") (pin "37") (pinfunction "37_37") (pintype "passive"))
      (node (ref "CF8.2") (pin "37") (pinfunction "37_37") (pintype "passive"))
    )
    (net (code "46") (name "UHF-TURNSTILE") (class "Default")
      (node (ref "CM1.3") (pin "RF-DOWN") (pinfunction "RF_RF-DOWN") (pintype "passive"))
      (node (ref "CM2.3") (pin "RF-DOWN") (pinfunction "RF_RF-DOWN") (pintype "passive"))
    )
    (net (code "47") (name "VBUS") (class "Default")
      (node (ref "C10") (pin "1") (pinfunction "1_1") (pintype "passive"))
      (node (ref "C11") (pin "1") (pinfunction "1_1") (pintype "passive"))
      (node (ref "C12") (pin "1") (pinfunction "1_1") (pintype "passive"))
      (node (ref "C5") (pin "1") (pinfunction "1_1") (pintype "passive"))
      (node (ref "C6") (pin "1") (pinfunction "1_1") (pintype "passive"))
      (node (ref "C7") (pin "1") (pinfunction "1_1") (pintype "passive"))
      (node (ref "C8") (pin "1") (pinfunction "1_1") (pintype "passive"))
      (node (ref "C9") (pin "1") (pinfunction "1_1") (pintype "passive"))
      (node (ref "CF1.2") (pin "23") (pinfunction "23_23") (pintype "passive"))
      (node (ref "CF1.2") (pin "24") (pinfunction "24_24") (pintype "passive"))
      (node (ref "CF1.2") (pin "25") (pinfunction "25_25") (pintype "passive"))
      (node (ref "CF1.2") (pin "26") (pinfunction "26_26") (pintype "passive"))
      (node (ref "CF2.2") (pin "23") (pinfunction "23_23") (pintype "passive"))
      (node (ref "CF2.2") (pin "24") (pinfunction "24_24") (pintype "passive"))
      (node (ref "CF2.2") (pin "25") (pinfunction "25_25") (pintype "passive"))
      (node (ref "CF2.2") (pin "26") (pinfunction "26_26") (pintype "passive"))
      (node (ref "CF3.2") (pin "23") (pinfunction "23_23") (pintype "passive"))
      (node (ref "CF3.2") (pin "24") (pinfunction "24_24") (pintype "passive"))
      (node (ref "CF3.2") (pin "25") (pinfunction "25_25") (pintype "passive"))
      (node (ref "CF3.2") (pin "26") (pinfunction "26_26") (pintype "passive"))
      (node (ref "CF4.2") (pin "23") (pinfunction "23_23") (pintype "passive"))
      (node (ref "CF4.2") (pin "24") (pinfunction "24_24") (pintype "passive"))
      (node (ref "CF4.2") (pin "25") (pinfunction "25_25") (pintype "passive"))
      (node (ref "CF4.2") (pin "26") (pinfunction "26_26") (pintype "passive"))
      (node (ref "CF5.2") (pin "23") (pinfunction "23_23") (pintype "passive"))
      (node (ref "CF5.2") (pin "24") (pinfunction "24_24") (pintype "passive"))
      (node (ref "CF5.2") (pin "25") (pinfunction "25_25") (pintype "passive"))
      (node (ref "CF5.2") (pin "26") (pinfunction "26_26") (pintype "passive"))
      (node (ref "CF6.2") (pin "23") (pinfunction "23_23") (pintype "passive"))
      (node (ref "CF6.2") (pin "24") (pinfunction "24_24") (pintype "passive"))
      (node (ref "CF6.2") (pin "25") (pinfunction "25_25") (pintype "passive"))
      (node (ref "CF6.2") (pin "26") (pinfunction "26_26") (pintype "passive"))
      (node (ref "CF7.2") (pin "23") (pinfunction "23_23") (pintype "passive"))
      (node (ref "CF7.2") (pin "24") (pinfunction "24_24") (pintype "passive"))
      (node (ref "CF7.2") (pin "25") (pinfunction "25_25") (pintype "passive"))
      (node (ref "CF7.2") (pin "26") (pinfunction "26_26") (pintype "passive"))
      (node (ref "CF8.2") (pin "23") (pinfunction "23_23") (pintype "passive"))
      (node (ref "CF8.2") (pin "24") (pinfunction "24_24") (pintype "passive"))
      (node (ref "CF8.2") (pin "25") (pinfunction "25_25") (pintype "passive"))
      (node (ref "CF8.2") (pin "26") (pinfunction "26_26") (pintype "passive"))
      (node (ref "J3") (pin "11") (pinfunction "11_11") (pintype "passive"))
      (node (ref "J3") (pin "12") (pinfunction "12_12") (pintype "passive"))
      (node (ref "J3") (pin "13") (pinfunction "13_13") (pintype "passive"))
    )
    (net (code "48") (name "unconnected-(FIDUCIAL1-PadFIDUCIAL)") (class "Default")
      (node (ref "FIDUCIAL1") (pin "FIDUCIAL") (pinfunction "FIDUCIAL_FIDUCIAL") (pintype "no_connect"))
    )
    (net (code "49") (name "unconnected-(FIDUCIAL2-PadFIDUCIAL)") (class "Default")
      (node (ref "FIDUCIAL2") (pin "FIDUCIAL") (pinfunction "FIDUCIAL_FIDUCIAL") (pintype "no_connect"))
    )
    (net (code "50") (name "unconnected-(FIDUCIAL3-PadFIDUCIAL)") (class "Default")
      (node (ref "FIDUCIAL3") (pin "FIDUCIAL") (pinfunction "FIDUCIAL_FIDUCIAL") (pintype "no_connect"))
    )
    (net (code "51") (name "unconnected-(J1-Pad1)") (class "Default")
      (node (ref "J1") (pin "1") (pinfunction "1_1") (pintype "passive"))
    )
    (net (code "52") (name "unconnected-(J1-Pad2)") (class "Default")
      (node (ref "J1") (pin "2") (pinfunction "2_2") (pintype "passive"))
    )
    (net (code "53") (name "unconnected-(J1-Pad3)") (class "Default")
      (node (ref "J1") (pin "3") (pinfunction "3_3") (pintype "passive"))
    )
    (net (code "54") (name "unconnected-(J1-Pad4)") (class "Default")
      (node (ref "J1") (pin "4") (pinfunction "4_4") (pintype "passive"))
    )
    (net (code "55") (name "unconnected-(J1-Pad5)") (class "Default")
      (node (ref "J1") (pin "5") (pinfunction "5_5") (pintype "passive"))
    )
    (net (code "56") (name "unconnected-(J1-Pad6)") (class "Default")
      (node (ref "J1") (pin "6") (pinfunction "6_6") (pintype "passive"))
    )
    (net (code "57") (name "unconnected-(J1-Pad7)") (class "Default")
      (node (ref "J1") (pin "7") (pinfunction "7_7") (pintype "passive"))
    )
    (net (code "58") (name "unconnected-(J1-Pad8)") (class "Default")
      (node (ref "J1") (pin "8") (pinfunction "8_8") (pintype "passive"))
    )
    (net (code "59") (name "unconnected-(J1-Pad9)") (class "Default")
      (node (ref "J1") (pin "9") (pinfunction "9_9") (pintype "passive"))
    )
    (net (code "60") (name "unconnected-(J1-Pad10)") (class "Default")
      (node (ref "J1") (pin "10") (pinfunction "10_10") (pintype "passive"))
    )
    (net (code "61") (name "~{SD}") (class "Default")
      (node (ref "CF1.2") (pin "39") (pinfunction "39_39") (pintype "passive"))
      (node (ref "CF1.2") (pin "40") (pinfunction "40_40") (pintype "passive"))
      (node (ref "CF2.2") (pin "39") (pinfunction "39_39") (pintype "passive"))
      (node (ref "CF2.2") (pin "40") (pinfunction "40_40") (pintype "passive"))
      (node (ref "CF3.2") (pin "39") (pinfunction "39_39") (pintype "passive"))
      (node (ref "CF3.2") (pin "40") (pinfunction "40_40") (pintype "passive"))
      (node (ref "CF4.2") (pin "39") (pinfunction "39_39") (pintype "passive"))
      (node (ref "CF4.2") (pin "40") (pinfunction "40_40") (pintype "passive"))
      (node (ref "CF5.2") (pin "39") (pinfunction "39_39") (pintype "passive"))
      (node (ref "CF5.2") (pin "40") (pinfunction "40_40") (pintype "passive"))
      (node (ref "CF6.2") (pin "39") (pinfunction "39_39") (pintype "passive"))
      (node (ref "CF6.2") (pin "40") (pinfunction "40_40") (pintype "passive"))
      (node (ref "CF7.2") (pin "39") (pinfunction "39_39") (pintype "passive"))
      (node (ref "CF7.2") (pin "40") (pinfunction "40_40") (pintype "passive"))
      (node (ref "CF8.2") (pin "39") (pinfunction "39_39") (pintype "passive"))
      (node (ref "CF8.2") (pin "40") (pinfunction "40_40") (pintype "passive"))
      (node (ref "J3") (pin "20") (pinfunction "20_20") (pintype "passive"))
    )
  )
)
